# controller.net
KiCad netlist of a schematic drawn in EAGLE
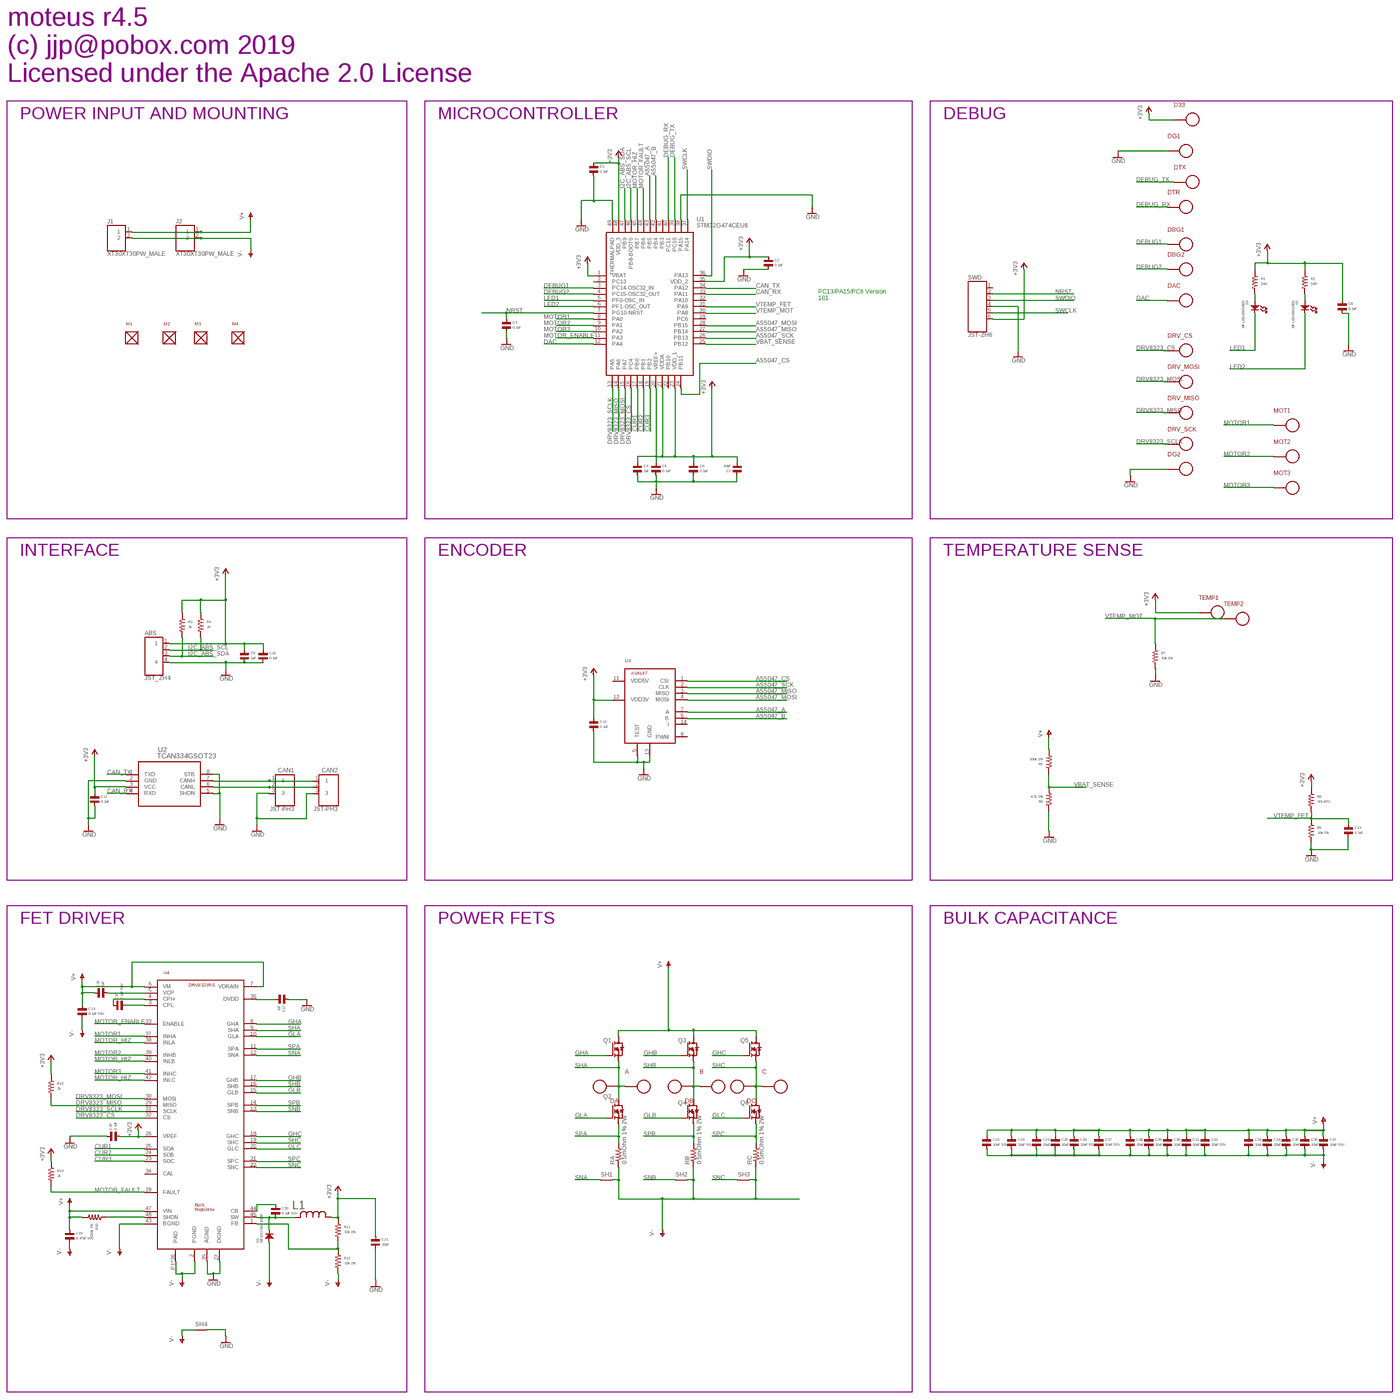
[diagram p0: schematic, sheet 1, overview]
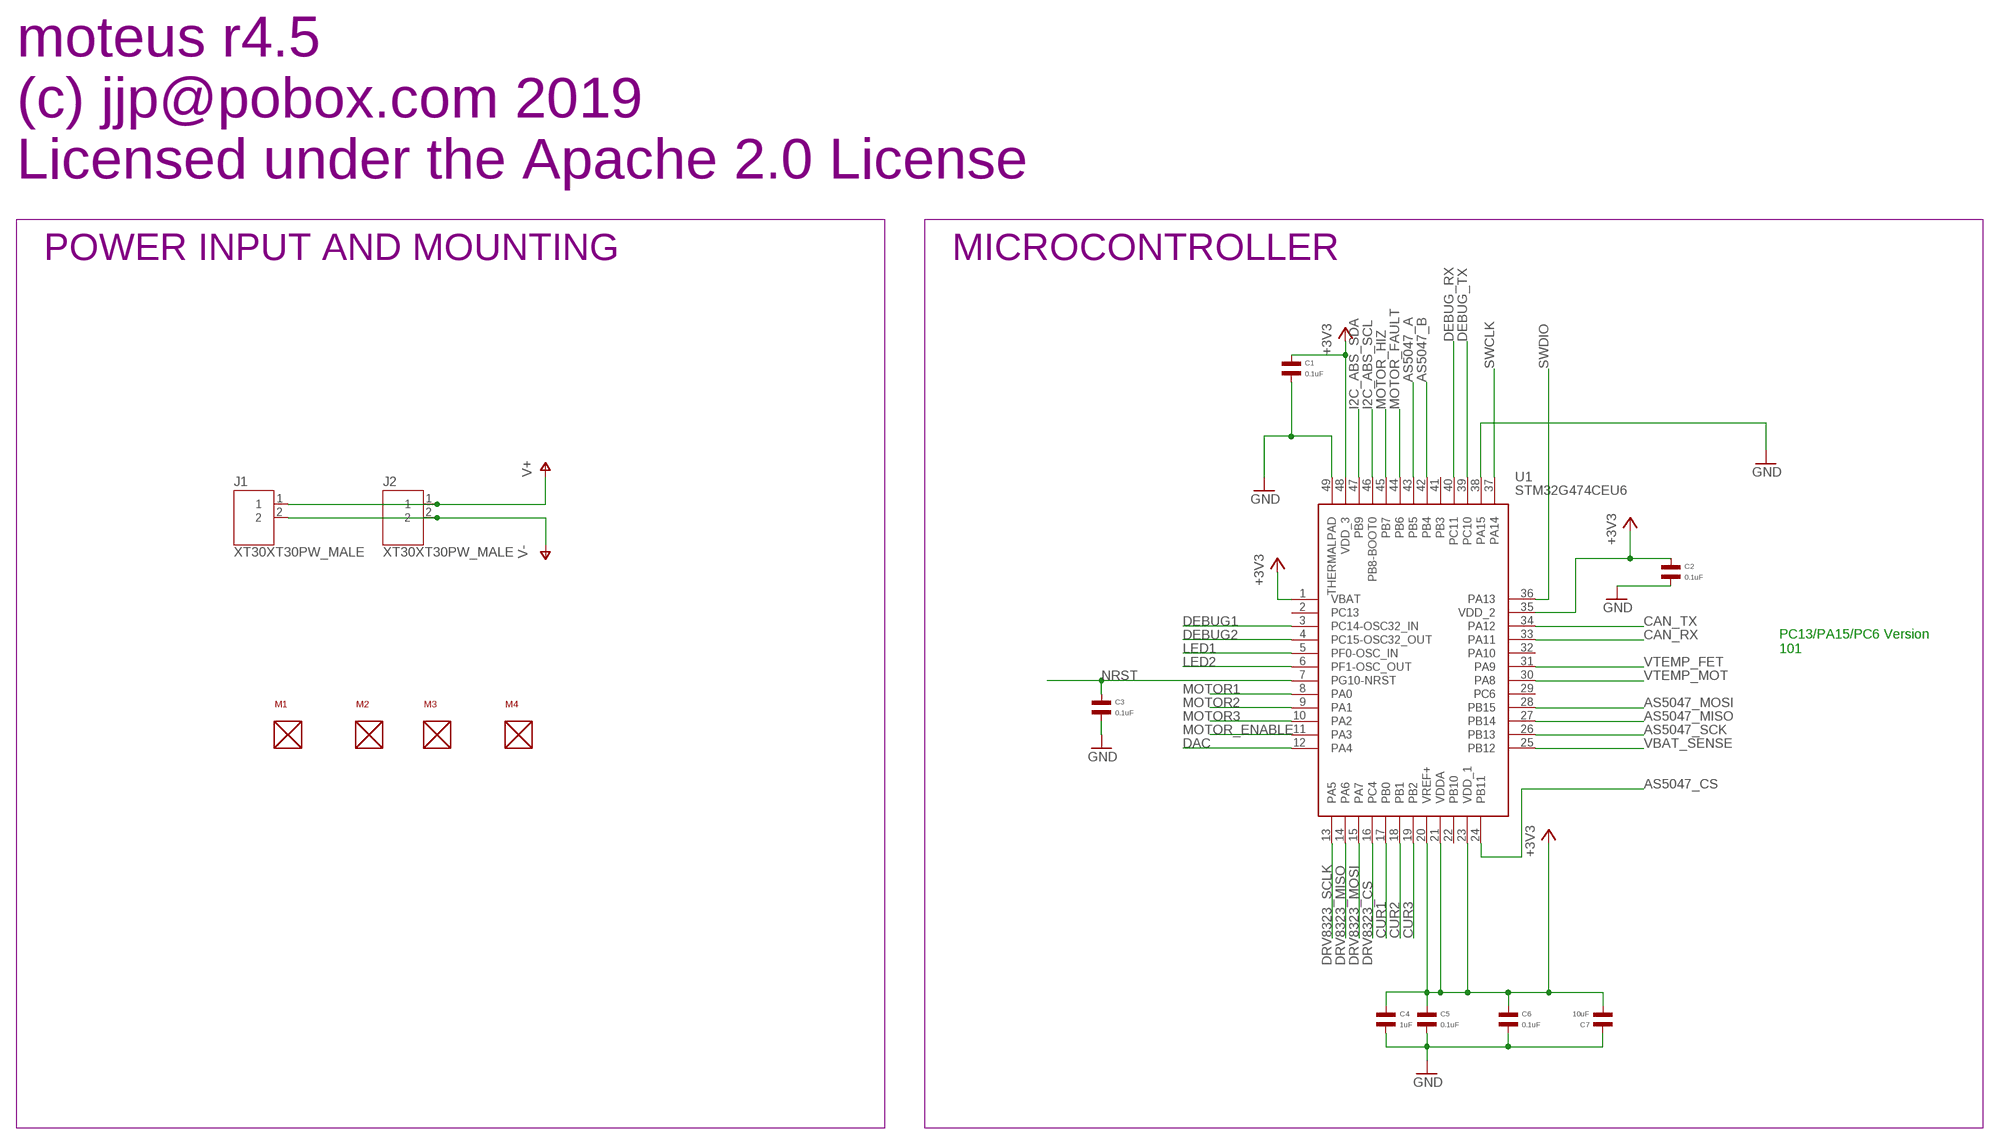
[diagram p1: schematic, sheet 1, part 1 of 4]
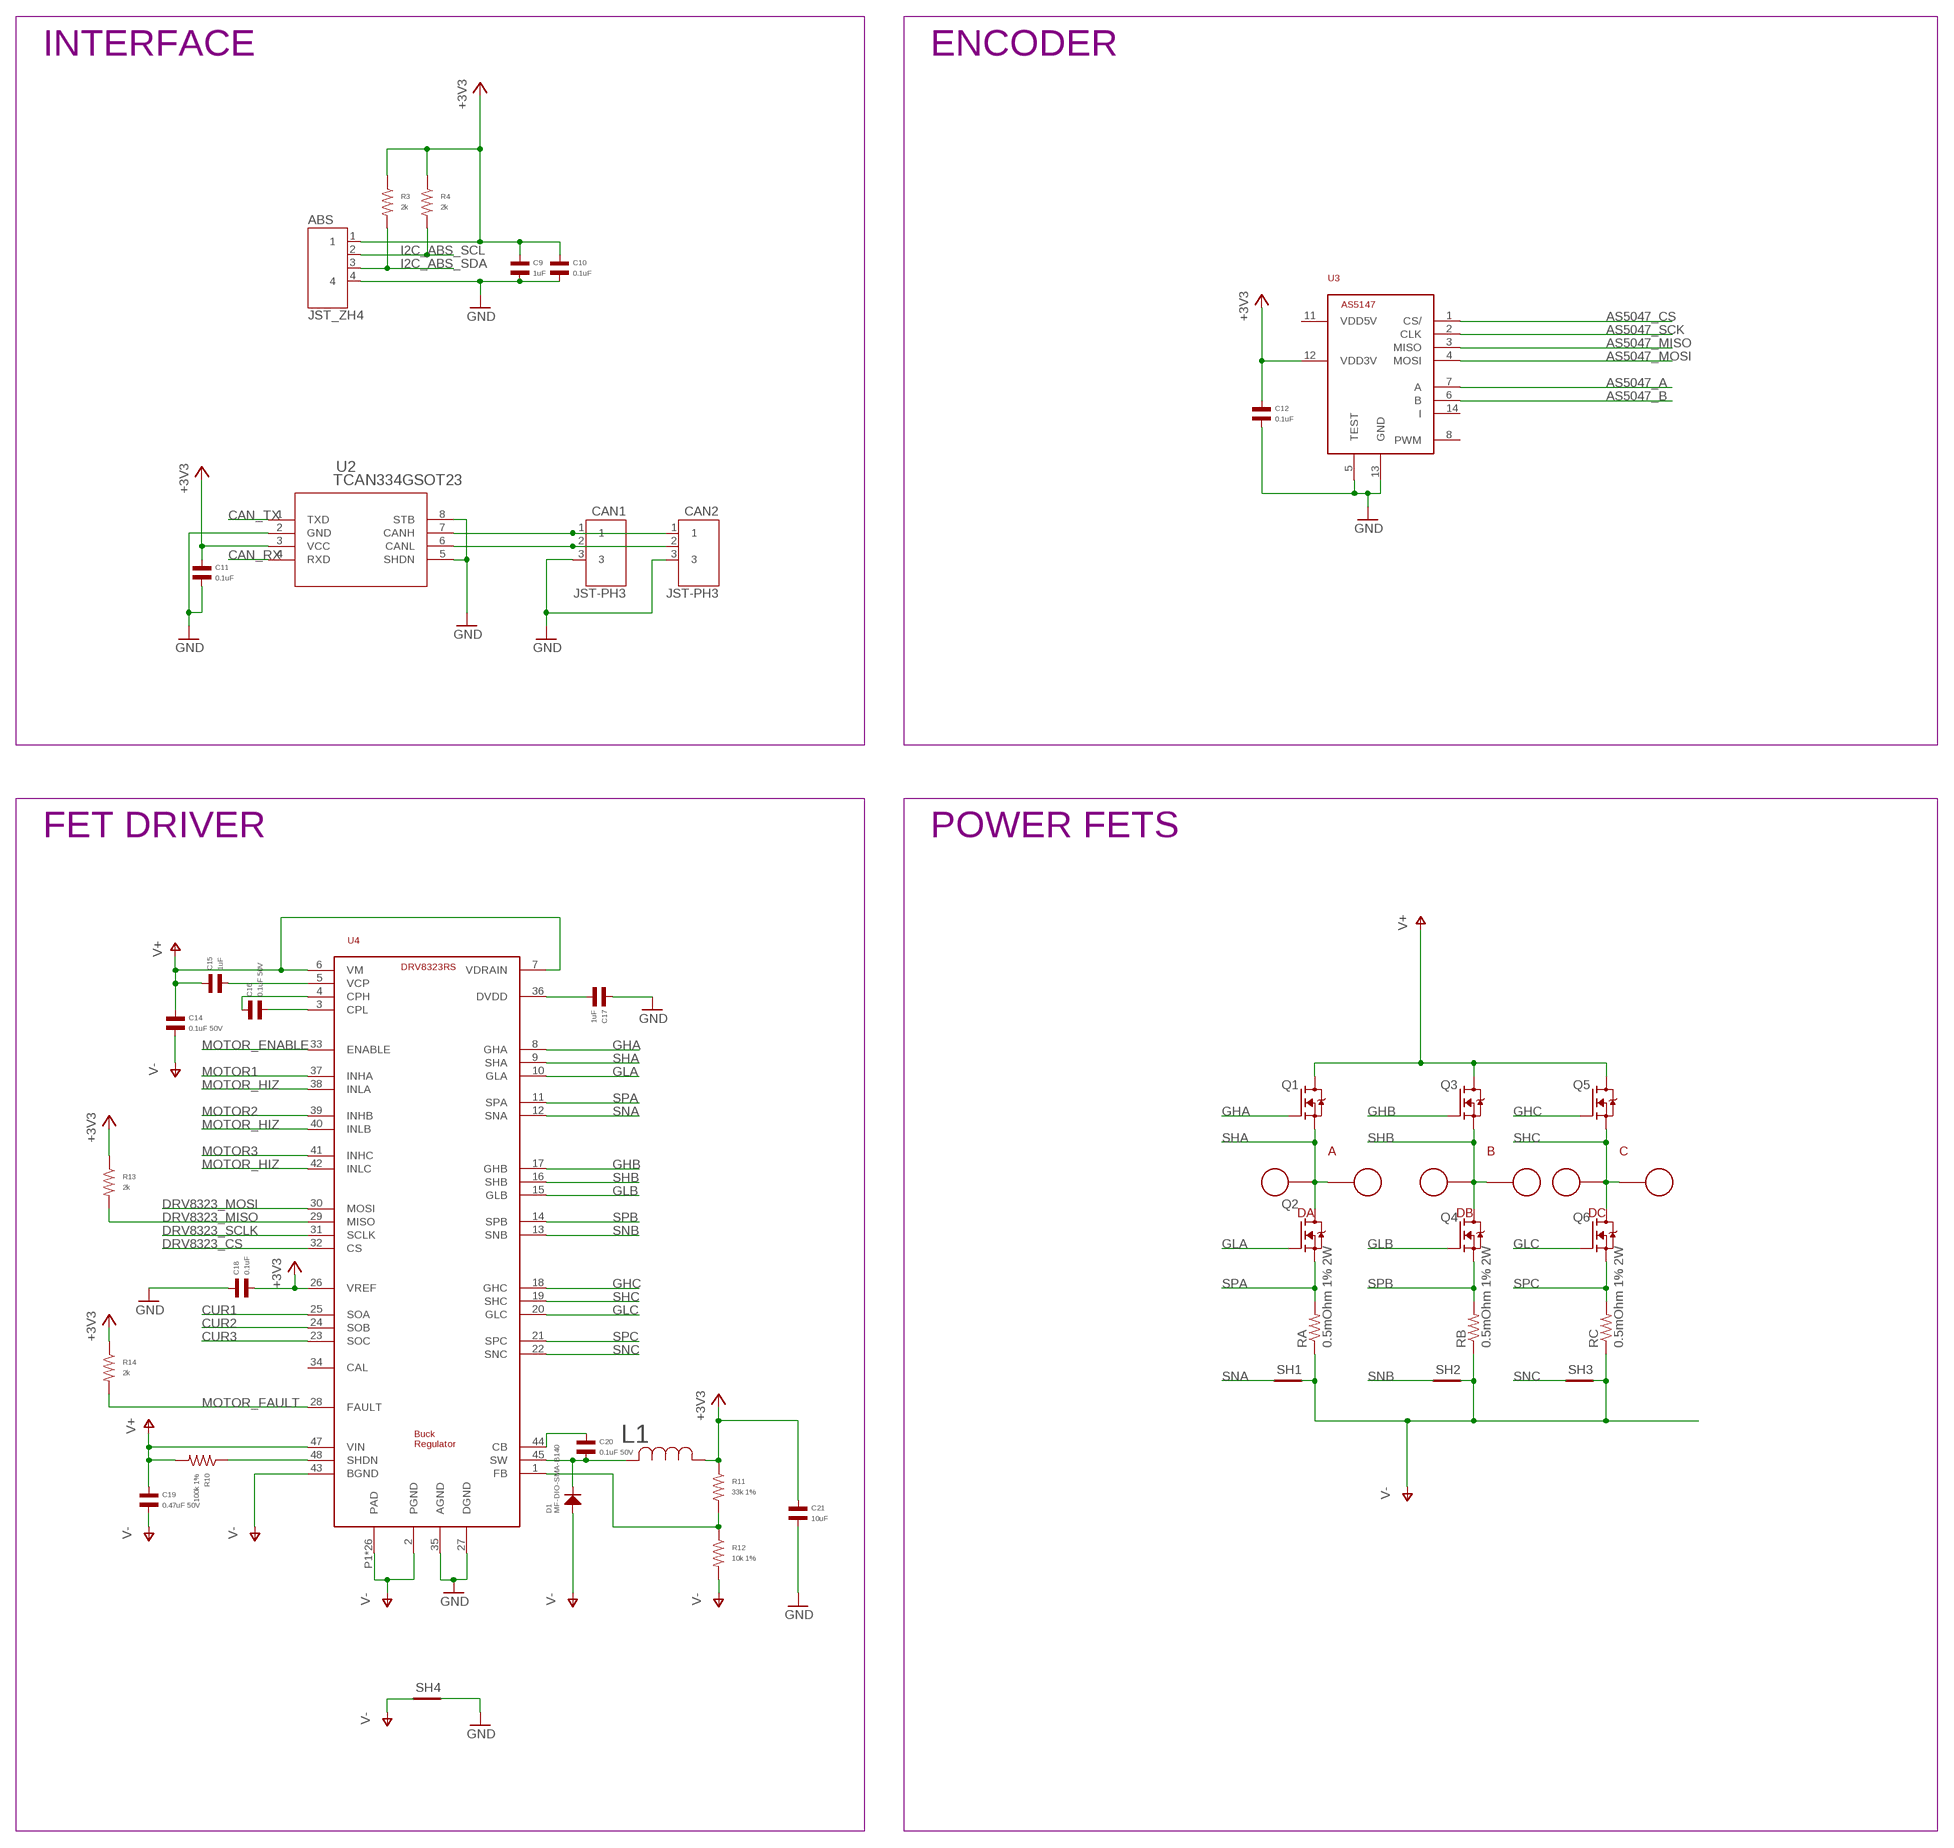
[diagram p2: schematic, sheet 1, part 2 of 4]
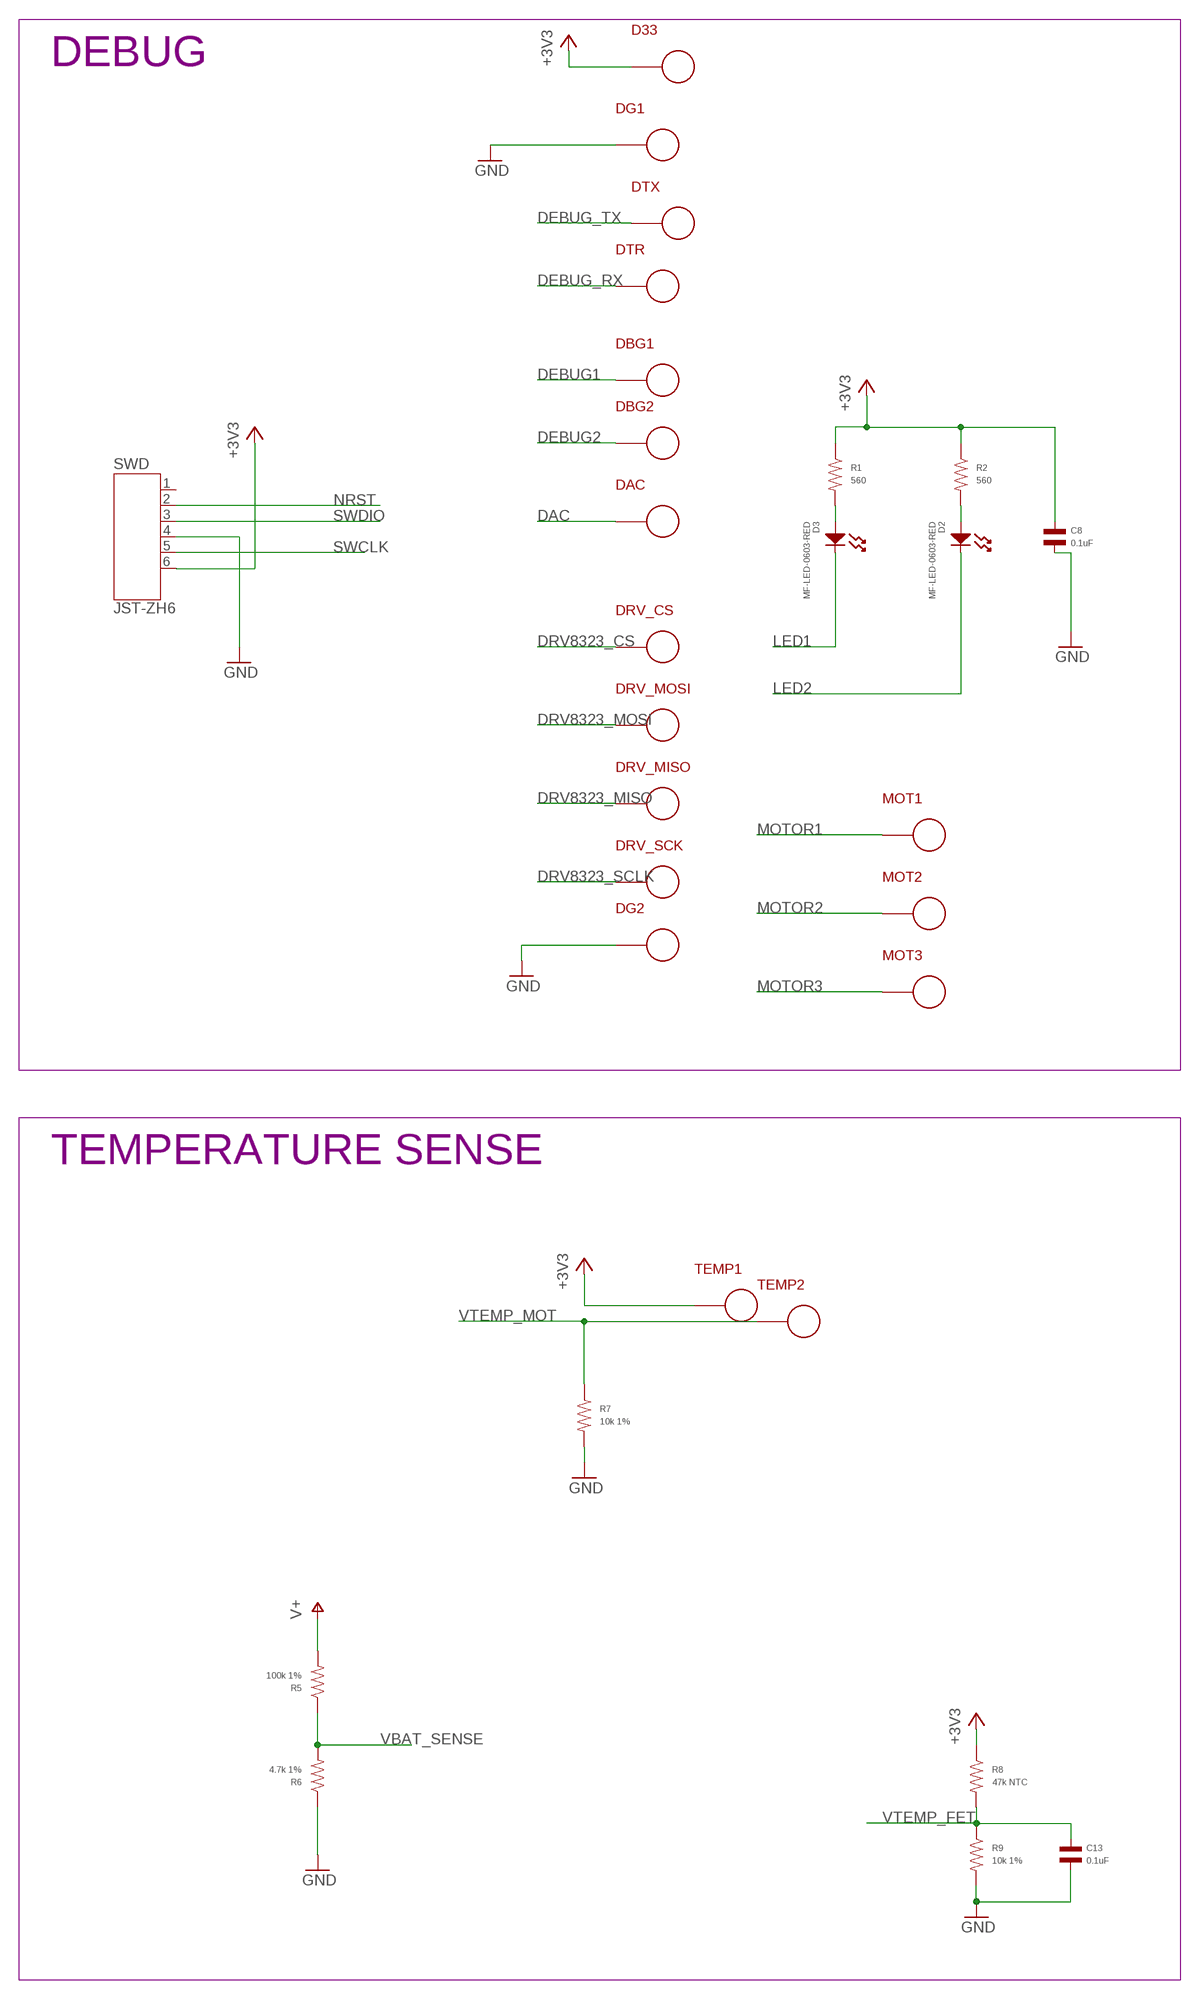
[diagram p3: schematic, sheet 1, part 3 of 4]
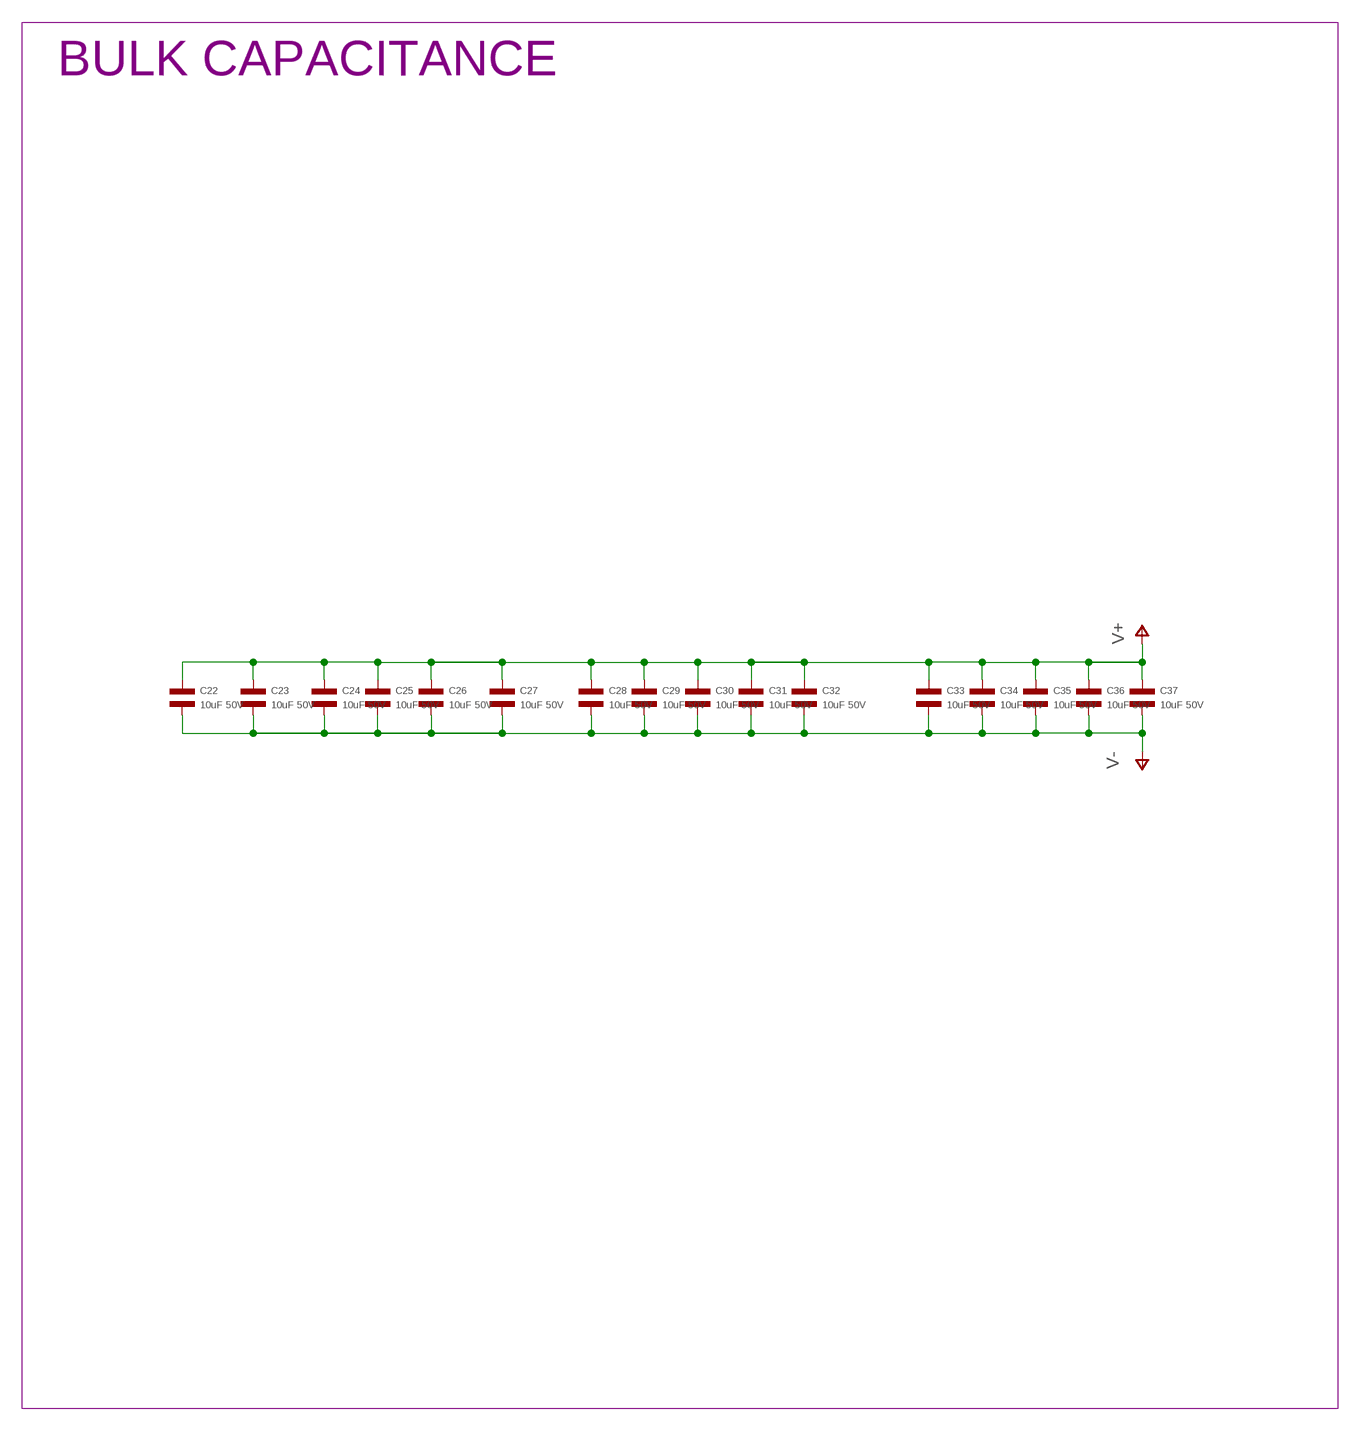
[diagram p4: schematic, sheet 1, part 4 of 4]

(export (version "E")
  (design (tool "Eeschema 10.0.6"))
  (components
    (comp (ref "A")
      (value "PAD16AWG_PAD")
      (footprint "eagle-import:16AWG_PAD")
      (libsource (lib "eagle-import") (part "PAD16AWG_PAD"))
    )
    (comp (ref "ABS")
      (value "JST_ZH4")
      (footprint "eagle-import:JST_S4B-ZR-SM4A-TF(LF)(SN)")
      (fields (field (name "MF") "JST") (field (name "MPN") "S4B-ZR-SM4A-TF(LF)(SN)"))
      (libsource (lib "eagle-import") (part "JST_ZH4"))
    )
    (comp (ref "B")
      (value "PAD16AWG_PAD")
      (footprint "eagle-import:16AWG_PAD")
      (libsource (lib "eagle-import") (part "PAD16AWG_PAD"))
    )
    (comp (ref "C")
      (value "PAD16AWG_PAD")
      (footprint "eagle-import:16AWG_PAD")
      (libsource (lib "eagle-import") (part "PAD16AWG_PAD"))
    )
    (comp (ref "C1")
      (value "0.1uF")
      (footprint "eagle-import:C0402")
      (fields (field (name "HOUSEPART") "YES") (field (name "MPN") "MF-CAP-0402-0.1uF"))
      (libsource (lib "eagle-import") (part "CAPACITOR_NP_0402"))
    )
    (comp (ref "C2")
      (value "0.1uF")
      (footprint "eagle-import:C0402")
      (fields (field (name "HOUSEPART") "YES") (field (name "MPN") "MF-CAP-0402-0.1uF"))
      (libsource (lib "eagle-import") (part "CAPACITOR_NP_0402"))
    )
    (comp (ref "C3")
      (value "0.1uF")
      (footprint "eagle-import:C0402")
      (fields (field (name "HOUSEPART") "YES") (field (name "MPN") "MF-CAP-0402-0.1uF"))
      (libsource (lib "eagle-import") (part "CAPACITOR_NP_0402"))
    )
    (comp (ref "C4")
      (value "1uF")
      (footprint "eagle-import:C0402")
      (fields (field (name "HOUSEPART") "YES") (field (name "MPN") "MF-CAP-0402-1uF"))
      (libsource (lib "eagle-import") (part "CAPACITOR_NP_0402"))
    )
    (comp (ref "C5")
      (value "0.1uF")
      (footprint "eagle-import:C0402")
      (fields (field (name "HOUSEPART") "YES") (field (name "MPN") "MF-CAP-0402-0.1uF"))
      (libsource (lib "eagle-import") (part "CAPACITOR_NP_0402"))
    )
    (comp (ref "C6")
      (value "0.1uF")
      (footprint "eagle-import:C0402")
      (fields (field (name "HOUSEPART") "YES") (field (name "MPN") "MF-CAP-0402-0.1uF"))
      (libsource (lib "eagle-import") (part "CAPACITOR_NP_0402"))
    )
    (comp (ref "C7")
      (value "10uF")
      (footprint "eagle-import:C1206")
      (fields (field (name "HOUSEPART") "YES") (field (name "MPN") "MF-CAP-1206-10uF"))
      (libsource (lib "eagle-import") (part "CAPACITOR_NP_1206"))
    )
    (comp (ref "C8")
      (value "0.1uF")
      (footprint "eagle-import:C0402")
      (fields (field (name "HOUSEPART") "YES") (field (name "MPN") "MF-CAP-0402-0.1uF"))
      (libsource (lib "eagle-import") (part "CAPACITOR_NP_0402"))
    )
    (comp (ref "C9")
      (value "1uF")
      (footprint "eagle-import:C0402")
      (fields (field (name "HOUSEPART") "YES") (field (name "MPN") "MF-CAP-0402-1uF"))
      (libsource (lib "eagle-import") (part "CAPACITOR_NP_0402"))
    )
    (comp (ref "C10")
      (value "0.1uF")
      (footprint "eagle-import:C0402")
      (fields (field (name "HOUSEPART") "YES") (field (name "MPN") "MF-CAP-0402-0.1uF"))
      (libsource (lib "eagle-import") (part "CAPACITOR_NP_0402"))
    )
    (comp (ref "C11")
      (value "0.1uF")
      (footprint "eagle-import:C0402")
      (fields (field (name "HOUSEPART") "YES") (field (name "MPN") "MF-CAP-0402-0.1uF"))
      (libsource (lib "eagle-import") (part "CAPACITOR_NP_0402"))
    )
    (comp (ref "C12")
      (value "0.1uF")
      (footprint "eagle-import:C0402")
      (fields (field (name "HOUSEPART") "YES") (field (name "MPN") "MF-CAP-0402-0.1uF"))
      (libsource (lib "eagle-import") (part "CAPACITOR_NP_0402"))
    )
    (comp (ref "C13")
      (value "0.1uF")
      (footprint "eagle-import:C0402")
      (fields (field (name "HOUSEPART") "YES") (field (name "MPN") "MF-CAP-0402-0.1uF"))
      (libsource (lib "eagle-import") (part "CAPACITOR_NP_0402"))
    )
    (comp (ref "C14")
      (value "0.1uF 50V")
      (footprint "eagle-import:C0402")
      (fields (field (name "MF") "TDK") (field (name "MPN") "CGA2B3X7R1H104K050BB"))
      (libsource (lib "eagle-import") (part "CAPACITOR_NP_0402"))
    )
    (comp (ref "C15")
      (value "1uF")
      (footprint "eagle-import:C0402")
      (fields (field (name "HOUSEPART") "YES") (field (name "MPN") "MF-CAP-0402-1uF"))
      (libsource (lib "eagle-import") (part "CAPACITOR_NP_0402"))
    )
    (comp (ref "C16")
      (value "0.1uF 50V")
      (footprint "eagle-import:C0402")
      (fields (field (name "MF") "TDK") (field (name "MPN") "CGA2B3X7R1H104K050BB"))
      (libsource (lib "eagle-import") (part "CAPACITOR_NP_0402"))
    )
    (comp (ref "C17")
      (value "1uF")
      (footprint "eagle-import:C0402")
      (fields (field (name "HOUSEPART") "YES") (field (name "MPN") "MF-CAP-0402-1uF"))
      (libsource (lib "eagle-import") (part "CAPACITOR_NP_0402"))
    )
    (comp (ref "C18")
      (value "0.1uF")
      (footprint "eagle-import:C0402")
      (fields (field (name "HOUSEPART") "YES") (field (name "MPN") "MF-CAP-0402-0.1uF"))
      (libsource (lib "eagle-import") (part "CAPACITOR_NP_0402"))
    )
    (comp (ref "C19")
      (value "0.47uF 50V")
      (footprint "eagle-import:C0402")
      (fields (field (name "MF") "Taiyo Yuden") (field (name "MPN") "UMK105ABJ474KV-F"))
      (libsource (lib "eagle-import") (part "CAPACITOR_NP_0402"))
    )
    (comp (ref "C20")
      (value "0.1uF 50V")
      (footprint "eagle-import:C0402")
      (fields (field (name "MF") "TDK") (field (name "MPN") "CGA2B3X7R1H104K050BB"))
      (libsource (lib "eagle-import") (part "CAPACITOR_NP_0402"))
    )
    (comp (ref "C21")
      (value "10uF")
      (footprint "eagle-import:C1206")
      (fields (field (name "HOUSEPART") "YES") (field (name "MPN") "MF-CAP-1206-10uF"))
      (libsource (lib "eagle-import") (part "CAPACITOR_NP_1206"))
    )
    (comp (ref "C22")
      (value "10uF 50V")
      (footprint "eagle-import:C1206")
      (fields (field (name "MF") "TDK") (field (name "MPN") "C3216X7R1H106K160AE"))
      (libsource (lib "eagle-import") (part "CAPACITOR_NP_1206"))
    )
    (comp (ref "C23")
      (value "10uF 50V")
      (footprint "eagle-import:C1206")
      (fields (field (name "MF") "TDK") (field (name "MPN") "C3216X7R1H106K160AE"))
      (libsource (lib "eagle-import") (part "CAPACITOR_NP_1206"))
    )
    (comp (ref "C24")
      (value "10uF 50V")
      (footprint "eagle-import:C1206")
      (fields (field (name "MF") "TDK") (field (name "MPN") "C3216X7R1H106K160AE"))
      (libsource (lib "eagle-import") (part "CAPACITOR_NP_1206"))
    )
    (comp (ref "C25")
      (value "10uF 50V")
      (footprint "eagle-import:C1206")
      (fields (field (name "MF") "TDK") (field (name "MPN") "C3216X7R1H106K160AE"))
      (libsource (lib "eagle-import") (part "CAPACITOR_NP_1206"))
    )
    (comp (ref "C26")
      (value "10uF 50V")
      (footprint "eagle-import:C1206")
      (fields (field (name "MF") "TDK") (field (name "MPN") "C3216X7R1H106K160AE"))
      (libsource (lib "eagle-import") (part "CAPACITOR_NP_1206"))
    )
    (comp (ref "C27")
      (value "10uF 50V")
      (footprint "eagle-import:C1206")
      (fields (field (name "MF") "TDK") (field (name "MPN") "C3216X7R1H106K160AE"))
      (libsource (lib "eagle-import") (part "CAPACITOR_NP_1206"))
    )
    (comp (ref "C28")
      (value "10uF 50V")
      (footprint "eagle-import:C1206")
      (fields (field (name "MF") "TDK") (field (name "MPN") "C3216X7R1H106K160AE"))
      (libsource (lib "eagle-import") (part "CAPACITOR_NP_1206"))
    )
    (comp (ref "C29")
      (value "10uF 50V")
      (footprint "eagle-import:C1206")
      (fields (field (name "MF") "TDK") (field (name "MPN") "C3216X7R1H106K160AE"))
      (libsource (lib "eagle-import") (part "CAPACITOR_NP_1206"))
    )
    (comp (ref "C30")
      (value "10uF 50V")
      (footprint "eagle-import:C1206")
      (fields (field (name "MF") "TDK") (field (name "MPN") "C3216X7R1H106K160AE"))
      (libsource (lib "eagle-import") (part "CAPACITOR_NP_1206"))
    )
    (comp (ref "C31")
      (value "10uF 50V")
      (footprint "eagle-import:C1206")
      (fields (field (name "MF") "TDK") (field (name "MPN") "C3216X7R1H106K160AE"))
      (libsource (lib "eagle-import") (part "CAPACITOR_NP_1206"))
    )
    (comp (ref "C32")
      (value "10uF 50V")
      (footprint "eagle-import:C1206")
      (fields (field (name "MF") "TDK") (field (name "MPN") "C3216X7R1H106K160AE"))
      (libsource (lib "eagle-import") (part "CAPACITOR_NP_1206"))
    )
    (comp (ref "C33")
      (value "10uF 50V")
      (footprint "eagle-import:C1206")
      (fields (field (name "MF") "TDK") (field (name "MPN") "C3216X7R1H106K160AE"))
      (libsource (lib "eagle-import") (part "CAPACITOR_NP_1206"))
    )
    (comp (ref "C34")
      (value "10uF 50V")
      (footprint "eagle-import:C1206")
      (fields (field (name "MF") "TDK") (field (name "MPN") "C3216X7R1H106K160AE"))
      (libsource (lib "eagle-import") (part "CAPACITOR_NP_1206"))
    )
    (comp (ref "C35")
      (value "10uF 50V")
      (footprint "eagle-import:C1206")
      (fields (field (name "MF") "TDK") (field (name "MPN") "C3216X7R1H106K160AE"))
      (libsource (lib "eagle-import") (part "CAPACITOR_NP_1206"))
    )
    (comp (ref "C36")
      (value "10uF 50V")
      (footprint "eagle-import:C1206")
      (fields (field (name "MF") "TDK") (field (name "MPN") "C3216X7R1H106K160AE"))
      (libsource (lib "eagle-import") (part "CAPACITOR_NP_1206"))
    )
    (comp (ref "C37")
      (value "10uF 50V")
      (footprint "eagle-import:C1206")
      (fields (field (name "MF") "TDK") (field (name "MPN") "C3216X7R1H106K160AE"))
      (libsource (lib "eagle-import") (part "CAPACITOR_NP_1206"))
    )
    (comp (ref "CAN1")
      (value "JST-PH3")
      (footprint "eagle-import:JST_S3B-PH-SM4-TB(LF)(SN)")
      (fields (field (name "MF") "JST") (field (name "MPN") "S3B-PH-SM4-TB(LF)(SN)"))
      (libsource (lib "eagle-import") (part "JST-PH3"))
    )
    (comp (ref "CAN2")
      (value "JST-PH3")
      (footprint "eagle-import:JST_S3B-PH-SM4-TB(LF)(SN)")
      (fields (field (name "MF") "JST") (field (name "MPN") "S3B-PH-SM4-TB(LF)(SN)"))
      (libsource (lib "eagle-import") (part "JST-PH3"))
    )
    (comp (ref "D1")
      (value "MF-DIO-SMA-B140")
      (footprint "eagle-import:SMA")
      (fields (field (name "HOUSEPART") "YES"))
      (libsource (lib "eagle-import") (part "DIODES_SMA_B140"))
    )
    (comp (ref "D2")
      (value "MF-LED-0603-RED")
      (footprint "eagle-import:LED0603")
      (fields (field (name "HOUSEPART") "YES") (field (name "MPN") "MF-LED-0603-GREEN"))
      (libsource (lib "eagle-import") (part "LED_SINGLE-0603-RED"))
    )
    (comp (ref "D3")
      (value "MF-LED-0603-RED")
      (footprint "eagle-import:LED0603")
      (fields (field (name "HOUSEPART") "YES"))
      (libsource (lib "eagle-import") (part "LED_SINGLE-0603-RED"))
    )
    (comp (ref "D33")
      (value "PAD24AWG_PAD")
      (footprint "eagle-import:24AWG_PAD")
      (libsource (lib "eagle-import") (part "PAD24AWG_PAD"))
    )
    (comp (ref "DA")
      (value "PAD24AWG_PAD")
      (footprint "eagle-import:24AWG_PAD")
      (libsource (lib "eagle-import") (part "PAD24AWG_PAD"))
    )
    (comp (ref "DAC")
      (value "PAD24AWG_PAD")
      (footprint "eagle-import:24AWG_PAD")
      (libsource (lib "eagle-import") (part "PAD24AWG_PAD"))
    )
    (comp (ref "DB")
      (value "PAD24AWG_PAD")
      (footprint "eagle-import:24AWG_PAD")
      (libsource (lib "eagle-import") (part "PAD24AWG_PAD"))
    )
    (comp (ref "DBG1")
      (value "PAD24AWG_PAD")
      (footprint "eagle-import:24AWG_PAD")
      (libsource (lib "eagle-import") (part "PAD24AWG_PAD"))
    )
    (comp (ref "DBG2")
      (value "PAD24AWG_PAD")
      (footprint "eagle-import:24AWG_PAD")
      (libsource (lib "eagle-import") (part "PAD24AWG_PAD"))
    )
    (comp (ref "DC")
      (value "PAD24AWG_PAD")
      (footprint "eagle-import:24AWG_PAD")
      (libsource (lib "eagle-import") (part "PAD24AWG_PAD"))
    )
    (comp (ref "DG1")
      (value "PAD24AWG_PAD")
      (footprint "eagle-import:24AWG_PAD")
      (libsource (lib "eagle-import") (part "PAD24AWG_PAD"))
    )
    (comp (ref "DG2")
      (value "PAD24AWG_PAD")
      (footprint "eagle-import:24AWG_PAD")
      (libsource (lib "eagle-import") (part "PAD24AWG_PAD"))
    )
    (comp (ref "DRV_CS")
      (value "PAD24AWG_PAD")
      (footprint "eagle-import:24AWG_PAD")
      (libsource (lib "eagle-import") (part "PAD24AWG_PAD"))
    )
    (comp (ref "DRV_MISO")
      (value "PAD24AWG_PAD")
      (footprint "eagle-import:24AWG_PAD")
      (libsource (lib "eagle-import") (part "PAD24AWG_PAD"))
    )
    (comp (ref "DRV_MOSI")
      (value "PAD24AWG_PAD")
      (footprint "eagle-import:24AWG_PAD")
      (libsource (lib "eagle-import") (part "PAD24AWG_PAD"))
    )
    (comp (ref "DRV_SCK")
      (value "PAD24AWG_PAD")
      (footprint "eagle-import:24AWG_PAD")
      (libsource (lib "eagle-import") (part "PAD24AWG_PAD"))
    )
    (comp (ref "DTR")
      (value "PAD24AWG_PAD")
      (footprint "eagle-import:24AWG_PAD")
      (libsource (lib "eagle-import") (part "PAD24AWG_PAD"))
    )
    (comp (ref "DTX")
      (value "PAD24AWG_PAD")
      (footprint "eagle-import:24AWG_PAD")
      (libsource (lib "eagle-import") (part "PAD24AWG_PAD"))
    )
    (comp (ref "J1")
      (value "XT30XT30PW_MALE")
      (footprint "eagle-import:XT30PW_MALE")
      (libsource (lib "eagle-import") (part "XT30XT30PW_MALE"))
    )
    (comp (ref "J2")
      (value "XT30XT30PW_MALE")
      (footprint "eagle-import:XT30PW_MALE")
      (libsource (lib "eagle-import") (part "XT30XT30PW_MALE"))
    )
    (comp (ref "L1")
      (value "SRN4018-220M")
      (footprint "eagle-import:IND_BOURNS_SRN4018")
      (fields (field (name "MANUFACTURER_PART_NUMBER") "SRN4018220M"))
      (libsource (lib "eagle-import") (part "SRN4018-220M"))
    )
    (comp (ref "M1")
      (value "MOUNT")
      (footprint "eagle-import:M2.5MOUNT")
      (libsource (lib "eagle-import") (part "MOUNT"))
    )
    (comp (ref "M2")
      (value "MOUNT")
      (footprint "eagle-import:M2.5MOUNT")
      (libsource (lib "eagle-import") (part "MOUNT"))
    )
    (comp (ref "M3")
      (value "MOUNT")
      (footprint "eagle-import:M2.5MOUNT")
      (libsource (lib "eagle-import") (part "MOUNT"))
    )
    (comp (ref "M4")
      (value "MOUNT")
      (footprint "eagle-import:M2.5MOUNT")
      (libsource (lib "eagle-import") (part "MOUNT"))
    )
    (comp (ref "MOT1")
      (value "PAD24AWG_PAD")
      (footprint "eagle-import:24AWG_PAD")
      (libsource (lib "eagle-import") (part "PAD24AWG_PAD"))
    )
    (comp (ref "MOT2")
      (value "PAD24AWG_PAD")
      (footprint "eagle-import:24AWG_PAD")
      (libsource (lib "eagle-import") (part "PAD24AWG_PAD"))
    )
    (comp (ref "MOT3")
      (value "PAD24AWG_PAD")
      (footprint "eagle-import:24AWG_PAD")
      (libsource (lib "eagle-import") (part "PAD24AWG_PAD"))
    )
    (comp (ref "Q1")
      (value "TPH1R204PLSOP_ADVANCE_8")
      (footprint "eagle-import:SOP_ADVANCE_8")
      (fields
        (field (name "MF") "Toshiba")
        (field (name "MPN") "TPH1R204PL")
        (field (name "MF_1") "Toshiba")
        (field (name "MPN_1") "TPH2R506PL,L1Q")
      )
      (libsource (lib "eagle-import") (part "TPH1R204PLSOP_ADVANCE_8"))
    )
    (comp (ref "Q2")
      (value "TPH1R204PLSOP_ADVANCE_8")
      (footprint "eagle-import:SOP_ADVANCE_8")
      (fields
        (field (name "MF") "Toshiba")
        (field (name "MPN") "TPH1R204PL")
        (field (name "MF_1") "Toshiba")
        (field (name "MPN_1") "TPH2R506PL,L1Q")
      )
      (libsource (lib "eagle-import") (part "TPH1R204PLSOP_ADVANCE_8"))
    )
    (comp (ref "Q3")
      (value "TPH1R204PLSOP_ADVANCE_8")
      (footprint "eagle-import:SOP_ADVANCE_8")
      (fields
        (field (name "MF") "Toshiba")
        (field (name "MPN") "TPH1R204PL")
        (field (name "MF_1") "Toshiba")
        (field (name "MPN_1") "TPH2R506PL,L1Q")
      )
      (libsource (lib "eagle-import") (part "TPH1R204PLSOP_ADVANCE_8"))
    )
    (comp (ref "Q4")
      (value "TPH1R204PLSOP_ADVANCE_8")
      (footprint "eagle-import:SOP_ADVANCE_8")
      (fields
        (field (name "MF") "Toshiba")
        (field (name "MPN") "TPH1R204PL")
        (field (name "MF_1") "Toshiba")
        (field (name "MPN_1") "TPH2R506PL,L1Q")
      )
      (libsource (lib "eagle-import") (part "TPH1R204PLSOP_ADVANCE_8"))
    )
    (comp (ref "Q5")
      (value "TPH1R204PLSOP_ADVANCE_8")
      (footprint "eagle-import:SOP_ADVANCE_8")
      (fields
        (field (name "MF") "Toshiba")
        (field (name "MPN") "TPH1R204PL")
        (field (name "MF_1") "Toshiba")
        (field (name "MPN_1") "TPH2R506PL,L1Q")
      )
      (libsource (lib "eagle-import") (part "TPH1R204PLSOP_ADVANCE_8"))
    )
    (comp (ref "Q6")
      (value "TPH1R204PLSOP_ADVANCE_8")
      (footprint "eagle-import:SOP_ADVANCE_8")
      (fields
        (field (name "MF") "Toshiba")
        (field (name "MPN") "TPH1R204PL")
        (field (name "MF_1") "Toshiba")
        (field (name "MPN_1") "TPH2R506PL,L1Q")
      )
      (libsource (lib "eagle-import") (part "TPH1R204PLSOP_ADVANCE_8"))
    )
    (comp (ref "R1")
      (value "560")
      (footprint "eagle-import:R0402")
      (fields (field (name "HOUSEPART") "1") (field (name "MPN") "MF-RES-0402-560"))
      (libsource (lib "eagle-import") (part "RESISTOR_0402"))
    )
    (comp (ref "R2")
      (value "560")
      (footprint "eagle-import:R0402")
      (fields (field (name "HOUSEPART") "1") (field (name "MPN") "MF-RES-0402-560"))
      (libsource (lib "eagle-import") (part "RESISTOR_0402"))
    )
    (comp (ref "R3")
      (value "2k")
      (footprint "eagle-import:R0402")
      (fields (field (name "HOUSEPART") "YES") (field (name "MPN") "MF-RES-0402-2K"))
      (libsource (lib "eagle-import") (part "RESISTOR_0402"))
    )
    (comp (ref "R4")
      (value "2k")
      (footprint "eagle-import:R0402")
      (fields (field (name "HOUSEPART") "YES") (field (name "MPN") "MF-RES-0402-2K"))
      (libsource (lib "eagle-import") (part "RESISTOR_0402"))
    )
    (comp (ref "R5")
      (value "100k 1%")
      (footprint "eagle-import:R0402")
      (fields (field (name "MF") "Panasonic") (field (name "MPN") "ERJ-2RKF1003X"))
      (libsource (lib "eagle-import") (part "RESISTOR_0402"))
    )
    (comp (ref "R6")
      (value "4.7k 1%")
      (footprint "eagle-import:R0402")
      (fields (field (name "MF") "Panasonic") (field (name "MPN") "ERJ-2RKF4701X"))
      (libsource (lib "eagle-import") (part "RESISTOR_0402"))
    )
    (comp (ref "R7")
      (value "10k 1%")
      (footprint "eagle-import:R0402")
      (fields (field (name "MF") "Panasonic") (field (name "MPN") "ERJ-2RKF1002X"))
      (libsource (lib "eagle-import") (part "RESISTOR_0402"))
    )
    (comp (ref "R8")
      (value "47k NTC")
      (footprint "eagle-import:R0402")
      (fields (field (name "MF") "Murata") (field (name "MPN") "NCP15WB473F03RC"))
      (libsource (lib "eagle-import") (part "RESISTOR_0402"))
    )
    (comp (ref "R9")
      (value "10k 1%")
      (footprint "eagle-import:R0402")
      (fields (field (name "MF") "Panasonic") (field (name "MPN") "ERJ-2RKF1002X"))
      (libsource (lib "eagle-import") (part "RESISTOR_0402"))
    )
    (comp (ref "R10")
      (value "100k 1%")
      (footprint "eagle-import:R0402")
      (fields (field (name "MF") "Panasonic") (field (name "MPN") "ERJ-2RKF1003X"))
      (libsource (lib "eagle-import") (part "RESISTOR_0402"))
    )
    (comp (ref "R11")
      (value "33k 1%")
      (footprint "eagle-import:R0402")
      (fields (field (name "MF") "Panasonic") (field (name "MPN") "ERJ-2RKF3302X"))
      (libsource (lib "eagle-import") (part "RESISTOR_0402"))
    )
    (comp (ref "R12")
      (value "10k 1%")
      (footprint "eagle-import:R0402")
      (fields (field (name "MF") "Panasonic") (field (name "MPN") "ERJ-2RKF1002X"))
      (libsource (lib "eagle-import") (part "RESISTOR_0402"))
    )
    (comp (ref "R13")
      (value "2k")
      (footprint "eagle-import:R0402")
      (fields (field (name "HOUSEPART") "YES") (field (name "MPN") "MF-RES-0402-2K"))
      (libsource (lib "eagle-import") (part "RESISTOR_0402"))
    )
    (comp (ref "R14")
      (value "2k")
      (footprint "eagle-import:R0402")
      (fields (field (name "HOUSEPART") "YES") (field (name "MPN") "MF-RES-0402-2K"))
      (libsource (lib "eagle-import") (part "RESISTOR_0402"))
    )
    (comp (ref "RA")
      (value "0.5mOhm 1% 2W")
      (footprint "eagle-import:M1206")
      (fields (field (name "MF") "Stackpole Electronics") (field (name "MPN") "HCS1206FTL500"))
      (libsource (lib "eagle-import") (part "R-US_M1206"))
    )
    (comp (ref "RB")
      (value "0.5mOhm 1% 2W")
      (footprint "eagle-import:M1206")
      (fields (field (name "MF") "Stackpole Electronics") (field (name "MPN") "HCS1206FTL500"))
      (libsource (lib "eagle-import") (part "R-US_M1206"))
    )
    (comp (ref "RC")
      (value "0.5mOhm 1% 2W")
      (footprint "eagle-import:M1206")
      (fields (field (name "MF") "Stackpole Electronics") (field (name "MPN") "HCS1206FTL500"))
      (libsource (lib "eagle-import") (part "R-US_M1206"))
    )
    (comp (ref "SH1")
      (value "SHORTT5")
      (footprint "eagle-import:SHORT_TOP-50")
      (libsource (lib "eagle-import") (part "SHORTT5"))
    )
    (comp (ref "SH2")
      (value "SHORTT5")
      (footprint "eagle-import:SHORT_TOP-50")
      (libsource (lib "eagle-import") (part "SHORTT5"))
    )
    (comp (ref "SH3")
      (value "SHORTT5")
      (footprint "eagle-import:SHORT_TOP-50")
      (libsource (lib "eagle-import") (part "SHORTT5"))
    )
    (comp (ref "SH4")
      (value "SHORTBIG")
      (footprint "eagle-import:SHORT_TOP-BIG")
      (libsource (lib "eagle-import") (part "SHORTBIG"))
    )
    (comp (ref "SWD")
      (value "JST-ZH6")
      (footprint "eagle-import:JST_S6B-ZR-SM4A-TF(LF)(SN)")
      (fields (field (name "MF") "JST") (field (name "MPN") "S6B-ZR-SM4A-TF(LF)(SN)"))
      (libsource (lib "eagle-import") (part "JST-ZH6"))
    )
    (comp (ref "TEMP1")
      (value "PAD24AWG_PAD")
      (footprint "eagle-import:24AWG_PAD")
      (libsource (lib "eagle-import") (part "PAD24AWG_PAD"))
    )
    (comp (ref "TEMP2")
      (value "PAD24AWG_PAD")
      (footprint "eagle-import:24AWG_PAD")
      (libsource (lib "eagle-import") (part "PAD24AWG_PAD"))
    )
    (comp (ref "U1")
      (value "STM32G474CEU6")
      (footprint "eagle-import:QFN50P700X700X60-49N")
      (fields (field (name "MOUSER_PART_NUMBER") "511-STM32G474CEU6"))
      (libsource (lib "eagle-import") (part "STM32G474CEU6"))
    )
    (comp (ref "U2")
      (value "TCAN334GSOT23")
      (footprint "eagle-import:SOT23-8")
      (fields (field (name "MF") "TI") (field (name "MPN") "TCAN334GDCNT"))
      (libsource (lib "eagle-import") (part "TCAN334GSOT23"))
    )
    (comp (ref "U3")
      (value "AS5147")
      (footprint "eagle-import:TSSOP14")
      (fields (field (name "MF") "AMS") (field (name "MPN") "AS5047P-ATSM"))
      (libsource (lib "eagle-import") (part "AS5147"))
    )
    (comp (ref "U4")
      (value "DRV8323RS")
      (footprint "eagle-import:PVQFN-N48")
      (fields (field (name "MF") "TI") (field (name "MPN") "DRV8323RSRGZR"))
      (libsource (lib "eagle-import") (part "DRV8323RS"))
    )
  )
  (nets
    (net (code "1") (name "+3V3") (class "Default")
      (node (ref "ABS") (pin "1") (pinfunction "1_1") (pintype "passive"))
      (node (ref "C1") (pin "P$1") (pinfunction "P$1_P$1") (pintype "passive"))
      (node (ref "C10") (pin "P$1") (pinfunction "P$1_P$1") (pintype "passive"))
      (node (ref "C11") (pin "P$1") (pinfunction "P$1_P$1") (pintype "passive"))
      (node (ref "C12") (pin "P$1") (pinfunction "P$1_P$1") (pintype "passive"))
      (node (ref "C18") (pin "P$2") (pinfunction "P$2_P$2") (pintype "passive"))
      (node (ref "C2") (pin "P$1") (pinfunction "P$1_P$1") (pintype "passive"))
      (node (ref "C21") (pin "P$1") (pinfunction "P$1_P$1") (pintype "passive"))
      (node (ref "C4") (pin "P$1") (pinfunction "P$1_P$1") (pintype "passive"))
      (node (ref "C5") (pin "P$1") (pinfunction "P$1_P$1") (pintype "passive"))
      (node (ref "C6") (pin "P$1") (pinfunction "P$1_P$1") (pintype "passive"))
      (node (ref "C7") (pin "P$2") (pinfunction "P$2_P$2") (pintype "passive"))
      (node (ref "C8") (pin "P$1") (pinfunction "P$1_P$1") (pintype "passive"))
      (node (ref "C9") (pin "P$1") (pinfunction "P$1_P$1") (pintype "passive"))
      (node (ref "D33") (pin "P$1") (pinfunction "P$1_P$1") (pintype "bidirectional"))
      (node (ref "L1") (pin "1") (pinfunction "1_1") (pintype "passive"))
      (node (ref "R1") (pin "P$1") (pinfunction "P$1_P$1") (pintype "passive"))
      (node (ref "R11") (pin "P$1") (pinfunction "P$1_P$1") (pintype "passive"))
      (node (ref "R13") (pin "P$1") (pinfunction "P$1_P$1") (pintype "passive"))
      (node (ref "R14") (pin "P$1") (pinfunction "P$1_P$1") (pintype "passive"))
      (node (ref "R2") (pin "P$1") (pinfunction "P$1_P$1") (pintype "passive"))
      (node (ref "R3") (pin "P$1") (pinfunction "P$1_P$1") (pintype "passive"))
      (node (ref "R4") (pin "P$1") (pinfunction "P$1_P$1") (pintype "passive"))
      (node (ref "R8") (pin "P$1") (pinfunction "P$1_P$1") (pintype "passive"))
      (node (ref "SWD") (pin "6") (pinfunction "6_6") (pintype "passive"))
      (node (ref "TEMP1") (pin "P$1") (pinfunction "P$1_P$1") (pintype "bidirectional"))
      (node (ref "U1") (pin "1") (pinfunction "VBAT_1") (pintype "bidirectional"))
      (node (ref "U1") (pin "20") (pinfunction "VREF+_20") (pintype "bidirectional"))
      (node (ref "U1") (pin "21") (pinfunction "VDDA_21") (pintype "bidirectional"))
      (node (ref "U1") (pin "23") (pinfunction "VDD_1_23") (pintype "bidirectional"))
      (node (ref "U1") (pin "35") (pinfunction "VDD_2_35") (pintype "bidirectional"))
      (node (ref "U1") (pin "48") (pinfunction "VDD_3_48") (pintype "bidirectional"))
      (node (ref "U2") (pin "3") (pinfunction "VCC_3") (pintype "power_in"))
      (node (ref "U3") (pin "12") (pinfunction "VDD3V_12") (pintype "bidirectional"))
      (node (ref "U4") (pin "26") (pinfunction "VREF_26") (pintype "bidirectional"))
    )
    (net (code "2") (name "/AS5047_A") (class "Default")
      (node (ref "U1") (pin "43") (pinfunction "PB5_43") (pintype "bidirectional"))
      (node (ref "U3") (pin "7") (pinfunction "A_7") (pintype "bidirectional"))
    )
    (net (code "3") (name "/AS5047_B") (class "Default")
      (node (ref "U1") (pin "42") (pinfunction "PB4_42") (pintype "bidirectional"))
      (node (ref "U3") (pin "6") (pinfunction "B_6") (pintype "bidirectional"))
    )
    (net (code "4") (name "/AS5047_CS") (class "Default")
      (node (ref "U1") (pin "24") (pinfunction "PB11_24") (pintype "bidirectional"))
      (node (ref "U3") (pin "1") (pinfunction "CS/_1") (pintype "bidirectional"))
    )
    (net (code "5") (name "/AS5047_MISO") (class "Default")
      (node (ref "U1") (pin "27") (pinfunction "PB14_27") (pintype "bidirectional"))
      (node (ref "U3") (pin "3") (pinfunction "MISO_3") (pintype "bidirectional"))
    )
    (net (code "6") (name "/AS5047_MOSI") (class "Default")
      (node (ref "U1") (pin "28") (pinfunction "PB15_28") (pintype "bidirectional"))
      (node (ref "U3") (pin "4") (pinfunction "MOSI_4") (pintype "bidirectional"))
    )
    (net (code "7") (name "/AS5047_SCK") (class "Default")
      (node (ref "U1") (pin "26") (pinfunction "PB13_26") (pintype "bidirectional"))
      (node (ref "U3") (pin "2") (pinfunction "CLK_2") (pintype "bidirectional"))
    )
    (net (code "8") (name "/CAN_RX") (class "Default")
      (node (ref "U1") (pin "33") (pinfunction "PA11_33") (pintype "bidirectional"))
      (node (ref "U2") (pin "4") (pinfunction "RXD_4") (pintype "output"))
    )
    (net (code "9") (name "/CAN_TX") (class "Default")
      (node (ref "U1") (pin "34") (pinfunction "PA12_34") (pintype "bidirectional"))
      (node (ref "U2") (pin "1") (pinfunction "TXD_1") (pintype "input"))
    )
    (net (code "10") (name "/CUR1") (class "Default")
      (node (ref "U1") (pin "17") (pinfunction "PB0_17") (pintype "bidirectional"))
      (node (ref "U4") (pin "25") (pinfunction "SOA_25") (pintype "bidirectional"))
    )
    (net (code "11") (name "/CUR2") (class "Default")
      (node (ref "U1") (pin "18") (pinfunction "PB1_18") (pintype "bidirectional"))
      (node (ref "U4") (pin "24") (pinfunction "SOB_24") (pintype "bidirectional"))
    )
    (net (code "12") (name "/CUR3") (class "Default")
      (node (ref "U1") (pin "19") (pinfunction "PB2_19") (pintype "bidirectional"))
      (node (ref "U4") (pin "23") (pinfunction "SOC_23") (pintype "bidirectional"))
    )
    (net (code "13") (name "/DAC") (class "Default")
      (node (ref "DAC") (pin "P$1") (pinfunction "P$1_P$1") (pintype "bidirectional"))
      (node (ref "U1") (pin "12") (pinfunction "PA4_12") (pintype "bidirectional"))
    )
    (net (code "14") (name "/DEBUG1") (class "Default")
      (node (ref "DBG1") (pin "P$1") (pinfunction "P$1_P$1") (pintype "bidirectional"))
      (node (ref "U1") (pin "3") (pinfunction "PC14-OSC32_IN_3") (pintype "bidirectional"))
    )
    (net (code "15") (name "/DEBUG2") (class "Default")
      (node (ref "DBG2") (pin "P$1") (pinfunction "P$1_P$1") (pintype "bidirectional"))
      (node (ref "U1") (pin "4") (pinfunction "PC15-OSC32_OUT_4") (pintype "bidirectional"))
    )
    (net (code "16") (name "/DEBUG_RX") (class "Default")
      (node (ref "DTR") (pin "P$1") (pinfunction "P$1_P$1") (pintype "bidirectional"))
      (node (ref "U1") (pin "40") (pinfunction "PC11_40") (pintype "bidirectional"))
    )
    (net (code "17") (name "/DEBUG_TX") (class "Default")
      (node (ref "DTX") (pin "P$1") (pinfunction "P$1_P$1") (pintype "bidirectional"))
      (node (ref "U1") (pin "39") (pinfunction "PC10_39") (pintype "bidirectional"))
    )
    (net (code "18") (name "/DRV8323_CS") (class "Default")
      (node (ref "DRV_CS") (pin "P$1") (pinfunction "P$1_P$1") (pintype "bidirectional"))
      (node (ref "U1") (pin "16") (pinfunction "PC4_16") (pintype "bidirectional"))
      (node (ref "U4") (pin "32") (pinfunction "CS_32") (pintype "bidirectional"))
    )
    (net (code "19") (name "/DRV8323_MISO") (class "Default")
      (node (ref "DRV_MISO") (pin "P$1") (pinfunction "P$1_P$1") (pintype "bidirectional"))
      (node (ref "R13") (pin "P$2") (pinfunction "P$2_P$2") (pintype "passive"))
      (node (ref "U1") (pin "14") (pinfunction "PA6_14") (pintype "bidirectional"))
      (node (ref "U4") (pin "29") (pinfunction "MISO_29") (pintype "bidirectional"))
    )
    (net (code "20") (name "/DRV8323_MOSI") (class "Default")
      (node (ref "DRV_MOSI") (pin "P$1") (pinfunction "P$1_P$1") (pintype "bidirectional"))
      (node (ref "U1") (pin "15") (pinfunction "PA7_15") (pintype "bidirectional"))
      (node (ref "U4") (pin "30") (pinfunction "MOSI_30") (pintype "bidirectional"))
    )
    (net (code "21") (name "/DRV8323_SCLK") (class "Default")
      (node (ref "DRV_SCK") (pin "P$1") (pinfunction "P$1_P$1") (pintype "bidirectional"))
      (node (ref "U1") (pin "13") (pinfunction "PA5_13") (pintype "bidirectional"))
      (node (ref "U4") (pin "31") (pinfunction "SCLK_31") (pintype "bidirectional"))
    )
    (net (code "22") (name "/GHA") (class "Default")
      (node (ref "Q1") (pin "4") (pinfunction "G_4") (pintype "passive"))
      (node (ref "U4") (pin "8") (pinfunction "GHA_8") (pintype "bidirectional"))
    )
    (net (code "23") (name "/GHB") (class "Default")
      (node (ref "Q3") (pin "4") (pinfunction "G_4") (pintype "passive"))
      (node (ref "U4") (pin "17") (pinfunction "GHB_17") (pintype "bidirectional"))
    )
    (net (code "24") (name "/GHC") (class "Default")
      (node (ref "Q5") (pin "4") (pinfunction "G_4") (pintype "passive"))
      (node (ref "U4") (pin "18") (pinfunction "GHC_18") (pintype "bidirectional"))
    )
    (net (code "25") (name "/GLA") (class "Default")
      (node (ref "Q2") (pin "4") (pinfunction "G_4") (pintype "passive"))
      (node (ref "U4") (pin "10") (pinfunction "GLA_10") (pintype "bidirectional"))
    )
    (net (code "26") (name "/GLB") (class "Default")
      (node (ref "Q4") (pin "4") (pinfunction "G_4") (pintype "passive"))
      (node (ref "U4") (pin "15") (pinfunction "GLB_15") (pintype "bidirectional"))
    )
    (net (code "27") (name "/GLC") (class "Default")
      (node (ref "Q6") (pin "4") (pinfunction "G_4") (pintype "passive"))
      (node (ref "U4") (pin "20") (pinfunction "GLC_20") (pintype "bidirectional"))
    )
    (net (code "28") (name "/I2C_ABS_SCL") (class "Default")
      (node (ref "ABS") (pin "2") (pinfunction "2_2") (pintype "passive"))
      (node (ref "R4") (pin "P$2") (pinfunction "P$2_P$2") (pintype "passive"))
      (node (ref "U1") (pin "46") (pinfunction "PB8-BOOT0_46") (pintype "bidirectional"))
    )
    (net (code "29") (name "/I2C_ABS_SDA") (class "Default")
      (node (ref "ABS") (pin "3") (pinfunction "3_3") (pintype "passive"))
      (node (ref "R3") (pin "P$2") (pinfunction "P$2_P$2") (pintype "passive"))
      (node (ref "U1") (pin "47") (pinfunction "PB9_47") (pintype "bidirectional"))
    )
    (net (code "30") (name "/LED1") (class "Default")
      (node (ref "D3") (pin "CATHODE") (pinfunction "CATHODE_CATHODE") (pintype "power_in"))
      (node (ref "U1") (pin "5") (pinfunction "PF0-OSC_IN_5") (pintype "bidirectional"))
    )
    (net (code "31") (name "/LED2") (class "Default")
      (node (ref "D2") (pin "CATHODE") (pinfunction "CATHODE_CATHODE") (pintype "power_in"))
      (node (ref "U1") (pin "6") (pinfunction "PF1-OSC_OUT_6") (pintype "bidirectional"))
    )
    (net (code "32") (name "/MOTOR1") (class "Default")
      (node (ref "MOT1") (pin "P$1") (pinfunction "P$1_P$1") (pintype "bidirectional"))
      (node (ref "U1") (pin "8") (pinfunction "PA0_8") (pintype "bidirectional"))
      (node (ref "U4") (pin "37") (pinfunction "INHA_37") (pintype "bidirectional"))
    )
    (net (code "33") (name "/MOTOR2") (class "Default")
      (node (ref "MOT2") (pin "P$1") (pinfunction "P$1_P$1") (pintype "bidirectional"))
      (node (ref "U1") (pin "9") (pinfunction "PA1_9") (pintype "bidirectional"))
      (node (ref "U4") (pin "39") (pinfunction "INHB_39") (pintype "bidirectional"))
    )
    (net (code "34") (name "/MOTOR3") (class "Default")
      (node (ref "MOT3") (pin "P$1") (pinfunction "P$1_P$1") (pintype "bidirectional"))
      (node (ref "U1") (pin "10") (pinfunction "PA2_10") (pintype "bidirectional"))
      (node (ref "U4") (pin "41") (pinfunction "INHC_41") (pintype "bidirectional"))
    )
    (net (code "35") (name "/MOTOR_ENABLE") (class "Default")
      (node (ref "U1") (pin "11") (pinfunction "PA3_11") (pintype "bidirectional"))
      (node (ref "U4") (pin "33") (pinfunction "ENABLE_33") (pintype "bidirectional"))
    )
    (net (code "36") (name "/MOTOR_FAULT") (class "Default")
      (node (ref "R14") (pin "P$2") (pinfunction "P$2_P$2") (pintype "passive"))
      (node (ref "U1") (pin "44") (pinfunction "PB6_44") (pintype "bidirectional"))
      (node (ref "U4") (pin "28") (pinfunction "FAULT_28") (pintype "bidirectional"))
    )
    (net (code "37") (name "/MOTOR_HIZ") (class "Default")
      (node (ref "U1") (pin "45") (pinfunction "PB7_45") (pintype "bidirectional"))
      (node (ref "U4") (pin "38") (pinfunction "INLA_38") (pintype "bidirectional"))
      (node (ref "U4") (pin "40") (pinfunction "INLB_40") (pintype "bidirectional"))
      (node (ref "U4") (pin "42") (pinfunction "INLC_42") (pintype "bidirectional"))
    )
    (net (code "38") (name "/NRST") (class "Default")
      (node (ref "C3") (pin "P$1") (pinfunction "P$1_P$1") (pintype "passive"))
      (node (ref "SWD") (pin "2") (pinfunction "2_2") (pintype "passive"))
      (node (ref "U1") (pin "7") (pinfunction "PG10-NRST_7") (pintype "bidirectional"))
    )
    (net (code "39") (name "/SHA") (class "Default")
      (node (ref "A") (pin "1") (pinfunction "P$1_1") (pintype "bidirectional"))
      (node (ref "DA") (pin "P$1") (pinfunction "P$1_P$1") (pintype "bidirectional"))
      (node (ref "Q1") (pin "1") (pinfunction "S_1") (pintype "passive"))
      (node (ref "Q1") (pin "2") (pinfunction "S_2") (pintype "passive"))
      (node (ref "Q1") (pin "3") (pinfunction "S_3") (pintype "passive"))
      (node (ref "Q2") (pin "5") (pinfunction "D_5") (pintype "passive"))
      (node (ref "Q2") (pin "6") (pinfunction "D_6") (pintype "passive"))
      (node (ref "Q2") (pin "7") (pinfunction "D_7") (pintype "passive"))
      (node (ref "Q2") (pin "8") (pinfunction "D_8") (pintype "passive"))
      (node (ref "Q2") (pin "PAD") (pinfunction "D_PAD") (pintype "passive"))
      (node (ref "U4") (pin "9") (pinfunction "SHA_9") (pintype "bidirectional"))
    )
    (net (code "40") (name "/SHB") (class "Default")
      (node (ref "B") (pin "1") (pinfunction "P$1_1") (pintype "bidirectional"))
      (node (ref "DB") (pin "P$1") (pinfunction "P$1_P$1") (pintype "bidirectional"))
      (node (ref "Q3") (pin "1") (pinfunction "S_1") (pintype "passive"))
      (node (ref "Q3") (pin "2") (pinfunction "S_2") (pintype "passive"))
      (node (ref "Q3") (pin "3") (pinfunction "S_3") (pintype "passive"))
      (node (ref "Q4") (pin "5") (pinfunction "D_5") (pintype "passive"))
      (node (ref "Q4") (pin "6") (pinfunction "D_6") (pintype "passive"))
      (node (ref "Q4") (pin "7") (pinfunction "D_7") (pintype "passive"))
      (node (ref "Q4") (pin "8") (pinfunction "D_8") (pintype "passive"))
      (node (ref "Q4") (pin "PAD") (pinfunction "D_PAD") (pintype "passive"))
      (node (ref "U4") (pin "16") (pinfunction "SHB_16") (pintype "bidirectional"))
    )
    (net (code "41") (name "/SHC") (class "Default")
      (node (ref "C") (pin "1") (pinfunction "P$1_1") (pintype "bidirectional"))
      (node (ref "DC") (pin "P$1") (pinfunction "P$1_P$1") (pintype "bidirectional"))
      (node (ref "Q5") (pin "1") (pinfunction "S_1") (pintype "passive"))
      (node (ref "Q5") (pin "2") (pinfunction "S_2") (pintype "passive"))
      (node (ref "Q5") (pin "3") (pinfunction "S_3") (pintype "passive"))
      (node (ref "Q6") (pin "5") (pinfunction "D_5") (pintype "passive"))
      (node (ref "Q6") (pin "6") (pinfunction "D_6") (pintype "passive"))
      (node (ref "Q6") (pin "7") (pinfunction "D_7") (pintype "passive"))
      (node (ref "Q6") (pin "8") (pinfunction "D_8") (pintype "passive"))
      (node (ref "Q6") (pin "PAD") (pinfunction "D_PAD") (pintype "passive"))
      (node (ref "U4") (pin "19") (pinfunction "SHC_19") (pintype "bidirectional"))
    )
    (net (code "42") (name "/SNA") (class "Default")
      (node (ref "SH1") (pin "1") (pinfunction "P$1_1") (pintype "bidirectional"))
      (node (ref "U4") (pin "12") (pinfunction "SNA_12") (pintype "bidirectional"))
    )
    (net (code "43") (name "/SNB") (class "Default")
      (node (ref "SH2") (pin "1") (pinfunction "P$1_1") (pintype "bidirectional"))
      (node (ref "U4") (pin "13") (pinfunction "SNB_13") (pintype "bidirectional"))
    )
    (net (code "44") (name "/SNC") (class "Default")
      (node (ref "SH3") (pin "1") (pinfunction "P$1_1") (pintype "bidirectional"))
      (node (ref "U4") (pin "22") (pinfunction "SNC_22") (pintype "bidirectional"))
    )
    (net (code "45") (name "/SPA") (class "Default")
      (node (ref "Q2") (pin "1") (pinfunction "S_1") (pintype "passive"))
      (node (ref "Q2") (pin "2") (pinfunction "S_2") (pintype "passive"))
      (node (ref "Q2") (pin "3") (pinfunction "S_3") (pintype "passive"))
      (node (ref "RA") (pin "2") (pinfunction "2_2") (pintype "passive"))
      (node (ref "U4") (pin "11") (pinfunction "SPA_11") (pintype "bidirectional"))
    )
    (net (code "46") (name "/SPB") (class "Default")
      (node (ref "Q4") (pin "1") (pinfunction "S_1") (pintype "passive"))
      (node (ref "Q4") (pin "2") (pinfunction "S_2") (pintype "passive"))
      (node (ref "Q4") (pin "3") (pinfunction "S_3") (pintype "passive"))
      (node (ref "RB") (pin "2") (pinfunction "2_2") (pintype "passive"))
      (node (ref "U4") (pin "14") (pinfunction "SPB_14") (pintype "bidirectional"))
    )
    (net (code "47") (name "/SPC") (class "Default")
      (node (ref "Q6") (pin "1") (pinfunction "S_1") (pintype "passive"))
      (node (ref "Q6") (pin "2") (pinfunction "S_2") (pintype "passive"))
      (node (ref "Q6") (pin "3") (pinfunction "S_3") (pintype "passive"))
      (node (ref "RC") (pin "2") (pinfunction "2_2") (pintype "passive"))
      (node (ref "U4") (pin "21") (pinfunction "SPC_21") (pintype "bidirectional"))
    )
    (net (code "48") (name "/SWCLK") (class "Default")
      (node (ref "SWD") (pin "5") (pinfunction "5_5") (pintype "passive"))
      (node (ref "U1") (pin "37") (pinfunction "PA14_37") (pintype "bidirectional"))
    )
    (net (code "49") (name "/SWDIO") (class "Default")
      (node (ref "SWD") (pin "3") (pinfunction "3_3") (pintype "passive"))
      (node (ref "U1") (pin "36") (pinfunction "PA13_36") (pintype "bidirectional"))
    )
    (net (code "50") (name "/VBAT_SENSE") (class "Default")
      (node (ref "R5") (pin "P$1") (pinfunction "P$1_P$1") (pintype "passive"))
      (node (ref "R6") (pin "P$2") (pinfunction "P$2_P$2") (pintype "passive"))
      (node (ref "U1") (pin "25") (pinfunction "PB12_25") (pintype "bidirectional"))
    )
    (net (code "51") (name "/VTEMP_FET") (class "Default")
      (node (ref "C13") (pin "P$1") (pinfunction "P$1_P$1") (pintype "passive"))
      (node (ref "R8") (pin "P$2") (pinfunction "P$2_P$2") (pintype "passive"))
      (node (ref "R9") (pin "P$1") (pinfunction "P$1_P$1") (pintype "passive"))
      (node (ref "U1") (pin "31") (pinfunction "PA9_31") (pintype "bidirectional"))
    )
    (net (code "52") (name "/VTEMP_MOT") (class "Default")
      (node (ref "R7") (pin "P$1") (pinfunction "P$1_P$1") (pintype "passive"))
      (node (ref "TEMP2") (pin "P$1") (pinfunction "P$1_P$1") (pintype "bidirectional"))
      (node (ref "U1") (pin "30") (pinfunction "PA8_30") (pintype "bidirectional"))
    )
    (net (code "53") (name "GND") (class "Default")
      (node (ref "ABS") (pin "4") (pinfunction "4_4") (pintype "passive"))
      (node (ref "C1") (pin "P$2") (pinfunction "P$2_P$2") (pintype "passive"))
      (node (ref "C10") (pin "P$2") (pinfunction "P$2_P$2") (pintype "passive"))
      (node (ref "C11") (pin "P$2") (pinfunction "P$2_P$2") (pintype "passive"))
      (node (ref "C12") (pin "P$2") (pinfunction "P$2_P$2") (pintype "passive"))
      (node (ref "C13") (pin "P$2") (pinfunction "P$2_P$2") (pintype "passive"))
      (node (ref "C17") (pin "P$1") (pinfunction "P$1_P$1") (pintype "passive"))
      (node (ref "C18") (pin "P$1") (pinfunction "P$1_P$1") (pintype "passive"))
      (node (ref "C2") (pin "P$2") (pinfunction "P$2_P$2") (pintype "passive"))
      (node (ref "C21") (pin "P$2") (pinfunction "P$2_P$2") (pintype "passive"))
      (node (ref "C3") (pin "P$2") (pinfunction "P$2_P$2") (pintype "passive"))
      (node (ref "C4") (pin "P$2") (pinfunction "P$2_P$2") (pintype "passive"))
      (node (ref "C5") (pin "P$2") (pinfunction "P$2_P$2") (pintype "passive"))
      (node (ref "C6") (pin "P$2") (pinfunction "P$2_P$2") (pintype "passive"))
      (node (ref "C7") (pin "P$1") (pinfunction "P$1_P$1") (pintype "passive"))
      (node (ref "C8") (pin "P$2") (pinfunction "P$2_P$2") (pintype "passive"))
      (node (ref "C9") (pin "P$2") (pinfunction "P$2_P$2") (pintype "passive"))
      (node (ref "CAN1") (pin "3") (pinfunction "3_3") (pintype "passive"))
      (node (ref "CAN2") (pin "3") (pinfunction "3_3") (pintype "passive"))
      (node (ref "DG1") (pin "P$1") (pinfunction "P$1_P$1") (pintype "bidirectional"))
      (node (ref "DG2") (pin "P$1") (pinfunction "P$1_P$1") (pintype "bidirectional"))
      (node (ref "R6") (pin "P$1") (pinfunction "P$1_P$1") (pintype "passive"))
      (node (ref "R7") (pin "P$2") (pinfunction "P$2_P$2") (pintype "passive"))
      (node (ref "R9") (pin "P$2") (pinfunction "P$2_P$2") (pintype "passive"))
      (node (ref "SH4") (pin "2") (pinfunction "P$2_2") (pintype "bidirectional"))
      (node (ref "SWD") (pin "4") (pinfunction "4_4") (pintype "passive"))
      (node (ref "U1") (pin "38") (pinfunction "PA15_38") (pintype "bidirectional"))
      (node (ref "U1") (pin "49") (pinfunction "THERMALPAD_49") (pintype "bidirectional"))
      (node (ref "U2") (pin "2") (pinfunction "GND_2") (pintype "power_in"))
      (node (ref "U2") (pin "5") (pinfunction "SHDN_5") (pintype "input"))
      (node (ref "U2") (pin "8") (pinfunction "STB_8") (pintype "input"))
      (node (ref "U3") (pin "13") (pinfunction "GND_13") (pintype "bidirectional"))
      (node (ref "U3") (pin "5") (pinfunction "TEST_5") (pintype "bidirectional"))
      (node (ref "U4") (pin "27") (pinfunction "DGND_27") (pintype "bidirectional"))
      (node (ref "U4") (pin "35") (pinfunction "AGND_35") (pintype "bidirectional"))
    )
    (net (code "54") (name "Net-(D2-PadANODE)") (class "Default")
      (node (ref "D2") (pin "ANODE") (pinfunction "ANODE_ANODE") (pintype "power_in"))
      (node (ref "R2") (pin "P$2") (pinfunction "P$2_P$2") (pintype "passive"))
    )
    (net (code "55") (name "Net-(D3-PadANODE)") (class "Default")
      (node (ref "D3") (pin "ANODE") (pinfunction "ANODE_ANODE") (pintype "power_in"))
      (node (ref "R1") (pin "P$2") (pinfunction "P$2_P$2") (pintype "passive"))
    )
    (net (code "56") (name "Net-(U2-CANH)") (class "Default")
      (node (ref "CAN1") (pin "1") (pinfunction "1_1") (pintype "passive"))
      (node (ref "CAN2") (pin "1") (pinfunction "1_1") (pintype "passive"))
      (node (ref "U2") (pin "7") (pinfunction "CANH_7") (pintype "bidirectional"))
    )
    (net (code "57") (name "Net-(U2-CANL)") (class "Default")
      (node (ref "CAN1") (pin "2") (pinfunction "2_2") (pintype "passive"))
      (node (ref "CAN2") (pin "2") (pinfunction "2_2") (pintype "passive"))
      (node (ref "U2") (pin "6") (pinfunction "CANL_6") (pintype "bidirectional"))
    )
    (net (code "58") (name "Net-(U4-CB)") (class "Default")
      (node (ref "C20") (pin "P$1") (pinfunction "P$1_P$1") (pintype "passive"))
      (node (ref "U4") (pin "44") (pinfunction "CB_44") (pintype "bidirectional"))
    )
    (net (code "59") (name "Net-(U4-CPH)") (class "Default")
      (node (ref "C16") (pin "P$1") (pinfunction "P$1_P$1") (pintype "passive"))
      (node (ref "U4") (pin "4") (pinfunction "CPH_4") (pintype "bidirectional"))
    )
    (net (code "60") (name "Net-(U4-CPL)") (class "Default")
      (node (ref "C16") (pin "P$2") (pinfunction "P$2_P$2") (pintype "passive"))
      (node (ref "U4") (pin "3") (pinfunction "CPL_3") (pintype "bidirectional"))
    )
    (net (code "61") (name "Net-(U4-DVDD)") (class "Default")
      (node (ref "C17") (pin "P$2") (pinfunction "P$2_P$2") (pintype "passive"))
      (node (ref "U4") (pin "36") (pinfunction "DVDD_36") (pintype "bidirectional"))
    )
    (net (code "62") (name "Net-(U4-FB)") (class "Default")
      (node (ref "R11") (pin "P$2") (pinfunction "P$2_P$2") (pintype "passive"))
      (node (ref "R12") (pin "P$1") (pinfunction "P$1_P$1") (pintype "passive"))
      (node (ref "U4") (pin "1") (pinfunction "FB_1") (pintype "bidirectional"))
    )
    (net (code "63") (name "Net-(U4-SHDN)") (class "Default")
      (node (ref "R10") (pin "P$1") (pinfunction "P$1_P$1") (pintype "passive"))
      (node (ref "U4") (pin "48") (pinfunction "SHDN_48") (pintype "bidirectional"))
    )
    (net (code "64") (name "Net-(U4-SW)") (class "Default")
      (node (ref "C20") (pin "P$2") (pinfunction "P$2_P$2") (pintype "passive"))
      (node (ref "D1") (pin "CATHODE") (pinfunction "CATHODE_CATHODE") (pintype "bidirectional"))
      (node (ref "L1") (pin "2") (pinfunction "2_2") (pintype "passive"))
      (node (ref "U4") (pin "45") (pinfunction "SW_45") (pintype "bidirectional"))
    )
    (net (code "65") (name "Net-(U4-VCP)") (class "Default")
      (node (ref "C15") (pin "P$2") (pinfunction "P$2_P$2") (pintype "passive"))
      (node (ref "U4") (pin "5") (pinfunction "VCP_5") (pintype "bidirectional"))
    )
    (net (code "66") (name "V+") (class "Default")
      (node (ref "C14") (pin "P$1") (pinfunction "P$1_P$1") (pintype "passive"))
      (node (ref "C15") (pin "P$1") (pinfunction "P$1_P$1") (pintype "passive"))
      (node (ref "C19") (pin "P$1") (pinfunction "P$1_P$1") (pintype "passive"))
      (node (ref "C22") (pin "P$1") (pinfunction "P$1_P$1") (pintype "passive"))
      (node (ref "C23") (pin "P$1") (pinfunction "P$1_P$1") (pintype "passive"))
      (node (ref "C24") (pin "P$1") (pinfunction "P$1_P$1") (pintype "passive"))
      (node (ref "C25") (pin "P$1") (pinfunction "P$1_P$1") (pintype "passive"))
      (node (ref "C26") (pin "P$1") (pinfunction "P$1_P$1") (pintype "passive"))
      (node (ref "C27") (pin "P$1") (pinfunction "P$1_P$1") (pintype "passive"))
      (node (ref "C28") (pin "P$1") (pinfunction "P$1_P$1") (pintype "passive"))
      (node (ref "C29") (pin "P$1") (pinfunction "P$1_P$1") (pintype "passive"))
      (node (ref "C30") (pin "P$1") (pinfunction "P$1_P$1") (pintype "passive"))
      (node (ref "C31") (pin "P$1") (pinfunction "P$1_P$1") (pintype "passive"))
      (node (ref "C32") (pin "P$1") (pinfunction "P$1_P$1") (pintype "passive"))
      (node (ref "C33") (pin "P$1") (pinfunction "P$1_P$1") (pintype "passive"))
      (node (ref "C34") (pin "P$1") (pinfunction "P$1_P$1") (pintype "passive"))
      (node (ref "C35") (pin "P$1") (pinfunction "P$1_P$1") (pintype "passive"))
      (node (ref "C36") (pin "P$1") (pinfunction "P$1_P$1") (pintype "passive"))
      (node (ref "C37") (pin "P$1") (pinfunction "P$1_P$1") (pintype "passive"))
      (node (ref "J1") (pin "1") (pinfunction "1_1") (pintype "passive"))
      (node (ref "J2") (pin "1") (pinfunction "1_1") (pintype "passive"))
      (node (ref "Q1") (pin "5") (pinfunction "D_5") (pintype "passive"))
      (node (ref "Q1") (pin "6") (pinfunction "D_6") (pintype "passive"))
      (node (ref "Q1") (pin "7") (pinfunction "D_7") (pintype "passive"))
      (node (ref "Q1") (pin "8") (pinfunction "D_8") (pintype "passive"))
      (node (ref "Q1") (pin "PAD") (pinfunction "D_PAD") (pintype "passive"))
      (node (ref "Q3") (pin "5") (pinfunction "D_5") (pintype "passive"))
      (node (ref "Q3") (pin "6") (pinfunction "D_6") (pintype "passive"))
      (node (ref "Q3") (pin "7") (pinfunction "D_7") (pintype "passive"))
      (node (ref "Q3") (pin "8") (pinfunction "D_8") (pintype "passive"))
      (node (ref "Q3") (pin "PAD") (pinfunction "D_PAD") (pintype "passive"))
      (node (ref "Q5") (pin "5") (pinfunction "D_5") (pintype "passive"))
      (node (ref "Q5") (pin "6") (pinfunction "D_6") (pintype "passive"))
      (node (ref "Q5") (pin "7") (pinfunction "D_7") (pintype "passive"))
      (node (ref "Q5") (pin "8") (pinfunction "D_8") (pintype "passive"))
      (node (ref "Q5") (pin "PAD") (pinfunction "D_PAD") (pintype "passive"))
      (node (ref "R10") (pin "P$2") (pinfunction "P$2_P$2") (pintype "passive"))
      (node (ref "R5") (pin "P$2") (pinfunction "P$2_P$2") (pintype "passive"))
      (node (ref "U4") (pin "47") (pinfunction "VIN_47") (pintype "bidirectional"))
      (node (ref "U4") (pin "6") (pinfunction "VM_6") (pintype "bidirectional"))
      (node (ref "U4") (pin "7") (pinfunction "VDRAIN_7") (pintype "bidirectional"))
    )
    (net (code "67") (name "V-") (class "Default")
      (node (ref "C14") (pin "P$2") (pinfunction "P$2_P$2") (pintype "passive"))
      (node (ref "C19") (pin "P$2") (pinfunction "P$2_P$2") (pintype "passive"))
      (node (ref "C22") (pin "P$2") (pinfunction "P$2_P$2") (pintype "passive"))
      (node (ref "C23") (pin "P$2") (pinfunction "P$2_P$2") (pintype "passive"))
      (node (ref "C24") (pin "P$2") (pinfunction "P$2_P$2") (pintype "passive"))
      (node (ref "C25") (pin "P$2") (pinfunction "P$2_P$2") (pintype "passive"))
      (node (ref "C26") (pin "P$2") (pinfunction "P$2_P$2") (pintype "passive"))
      (node (ref "C27") (pin "P$2") (pinfunction "P$2_P$2") (pintype "passive"))
      (node (ref "C28") (pin "P$2") (pinfunction "P$2_P$2") (pintype "passive"))
      (node (ref "C29") (pin "P$2") (pinfunction "P$2_P$2") (pintype "passive"))
      (node (ref "C30") (pin "P$2") (pinfunction "P$2_P$2") (pintype "passive"))
      (node (ref "C31") (pin "P$2") (pinfunction "P$2_P$2") (pintype "passive"))
      (node (ref "C32") (pin "P$2") (pinfunction "P$2_P$2") (pintype "passive"))
      (node (ref "C33") (pin "P$2") (pinfunction "P$2_P$2") (pintype "passive"))
      (node (ref "C34") (pin "P$2") (pinfunction "P$2_P$2") (pintype "passive"))
      (node (ref "C35") (pin "P$2") (pinfunction "P$2_P$2") (pintype "passive"))
      (node (ref "C36") (pin "P$2") (pinfunction "P$2_P$2") (pintype "passive"))
      (node (ref "C37") (pin "P$2") (pinfunction "P$2_P$2") (pintype "passive"))
      (node (ref "D1") (pin "ANODE") (pinfunction "ANODE_ANODE") (pintype "bidirectional"))
      (node (ref "J1") (pin "2") (pinfunction "2_2") (pintype "passive"))
      (node (ref "J2") (pin "2") (pinfunction "2_2") (pintype "passive"))
      (node (ref "R12") (pin "P$2") (pinfunction "P$2_P$2") (pintype "passive"))
      (node (ref "RA") (pin "1") (pinfunction "1_1") (pintype "passive"))
      (node (ref "RB") (pin "1") (pinfunction "1_1") (pintype "passive"))
      (node (ref "RC") (pin "1") (pinfunction "1_1") (pintype "passive"))
      (node (ref "SH1") (pin "2") (pinfunction "P$2_2") (pintype "bidirectional"))
      (node (ref "SH2") (pin "2") (pinfunction "P$2_2") (pintype "bidirectional"))
      (node (ref "SH3") (pin "2") (pinfunction "P$2_2") (pintype "bidirectional"))
      (node (ref "SH4") (pin "1") (pinfunction "P$1_1") (pintype "bidirectional"))
      (node (ref "U4") (pin "2") (pinfunction "PGND_2") (pintype "bidirectional"))
      (node (ref "U4") (pin "43") (pinfunction "BGND_43") (pintype "bidirectional"))
      (node (ref "U4") (pin "P1") (pinfunction "PAD_P1") (pintype "bidirectional"))
      (node (ref "U4") (pin "P10") (pinfunction "PAD_P10") (pintype "bidirectional"))
      (node (ref "U4") (pin "P11") (pinfunction "PAD_P11") (pintype "bidirectional"))
      (node (ref "U4") (pin "P12") (pinfunction "PAD_P12") (pintype "bidirectional"))
      (node (ref "U4") (pin "P13") (pinfunction "PAD_P13") (pintype "bidirectional"))
      (node (ref "U4") (pin "P14") (pinfunction "PAD_P14") (pintype "bidirectional"))
      (node (ref "U4") (pin "P15") (pinfunction "PAD_P15") (pintype "bidirectional"))
      (node (ref "U4") (pin "P16") (pinfunction "PAD_P16") (pintype "bidirectional"))
      (node (ref "U4") (pin "P17") (pinfunction "PAD_P17") (pintype "bidirectional"))
      (node (ref "U4") (pin "P18") (pinfunction "PAD_P18") (pintype "bidirectional"))
      (node (ref "U4") (pin "P19") (pinfunction "PAD_P19") (pintype "bidirectional"))
      (node (ref "U4") (pin "P2") (pinfunction "PAD_P2") (pintype "bidirectional"))
      (node (ref "U4") (pin "P20") (pinfunction "PAD_P20") (pintype "bidirectional"))
      (node (ref "U4") (pin "P21") (pinfunction "PAD_P21") (pintype "bidirectional"))
      (node (ref "U4") (pin "P22") (pinfunction "PAD_P22") (pintype "bidirectional"))
      (node (ref "U4") (pin "P23") (pinfunction "PAD_P23") (pintype "bidirectional"))
      (node (ref "U4") (pin "P24") (pinfunction "PAD_P24") (pintype "bidirectional"))
      (node (ref "U4") (pin "P25") (pinfunction "PAD_P25") (pintype "bidirectional"))
      (node (ref "U4") (pin "P3") (pinfunction "PAD_P3") (pintype "bidirectional"))
      (node (ref "U4") (pin "P4") (pinfunction "PAD_P4") (pintype "bidirectional"))
      (node (ref "U4") (pin "P5") (pinfunction "PAD_P5") (pintype "bidirectional"))
      (node (ref "U4") (pin "P6") (pinfunction "PAD_P6") (pintype "bidirectional"))
      (node (ref "U4") (pin "P7") (pinfunction "PAD_P7") (pintype "bidirectional"))
      (node (ref "U4") (pin "P8") (pinfunction "PAD_P8") (pintype "bidirectional"))
      (node (ref "U4") (pin "P9") (pinfunction "PAD_P9") (pintype "bidirectional"))
      (node (ref "U4") (pin "PAD") (pinfunction "PAD_PAD") (pintype "bidirectional"))
    )
    (net (code "68") (name "unconnected-(SWD-Pad1)") (class "Default")
      (node (ref "SWD") (pin "1") (pinfunction "1_1") (pintype "passive"))
    )
    (net (code "69") (name "unconnected-(U1-PA10-Pad32)") (class "Default")
      (node (ref "U1") (pin "32") (pinfunction "PA10_32") (pintype "bidirectional"))
    )
    (net (code "70") (name "unconnected-(U1-PB3-Pad41)") (class "Default")
      (node (ref "U1") (pin "41") (pinfunction "PB3_41") (pintype "bidirectional"))
    )
    (net (code "71") (name "unconnected-(U1-PB10-Pad22)") (class "Default")
      (node (ref "U1") (pin "22") (pinfunction "PB10_22") (pintype "bidirectional"))
    )
    (net (code "72") (name "unconnected-(U1-PC6-Pad29)") (class "Default")
      (node (ref "U1") (pin "29") (pinfunction "PC6_29") (pintype "bidirectional"))
    )
    (net (code "73") (name "unconnected-(U1-PC13-Pad2)") (class "Default")
      (node (ref "U1") (pin "2") (pinfunction "PC13_2") (pintype "bidirectional"))
    )
    (net (code "74") (name "unconnected-(U3-I-Pad14)") (class "Default")
      (node (ref "U3") (pin "14") (pinfunction "I_14") (pintype "bidirectional"))
    )
    (net (code "75") (name "unconnected-(U3-PWM-Pad8)") (class "Default")
      (node (ref "U3") (pin "8") (pinfunction "PWM_8") (pintype "bidirectional"))
    )
    (net (code "76") (name "unconnected-(U3-VDD5V-Pad11)") (class "Default")
      (node (ref "U3") (pin "11") (pinfunction "VDD5V_11") (pintype "bidirectional"))
    )
    (net (code "77") (name "unconnected-(U4-CAL-Pad34)") (class "Default")
      (node (ref "U4") (pin "34") (pinfunction "CAL_34") (pintype "bidirectional"))
    )
  )
)
